# OutputIndicator_v1p4.net
KiCad netlist of a schematic drawn in EAGLE
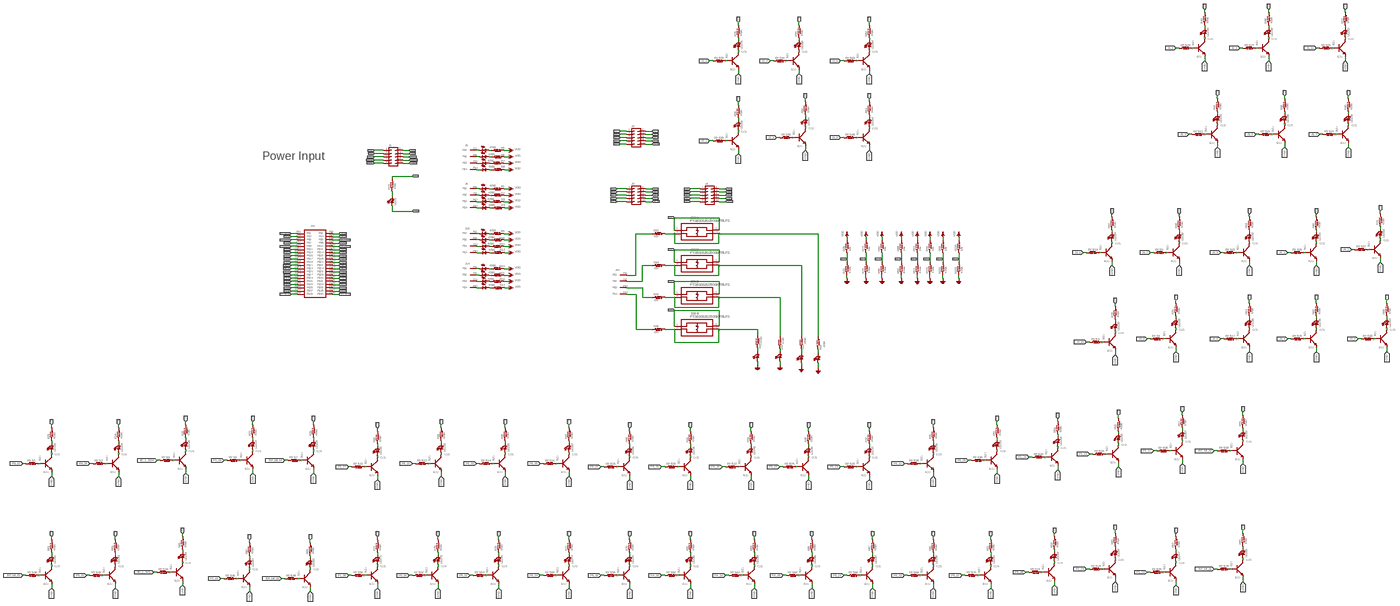
[diagram p0: schematic, sheet 1, overview]
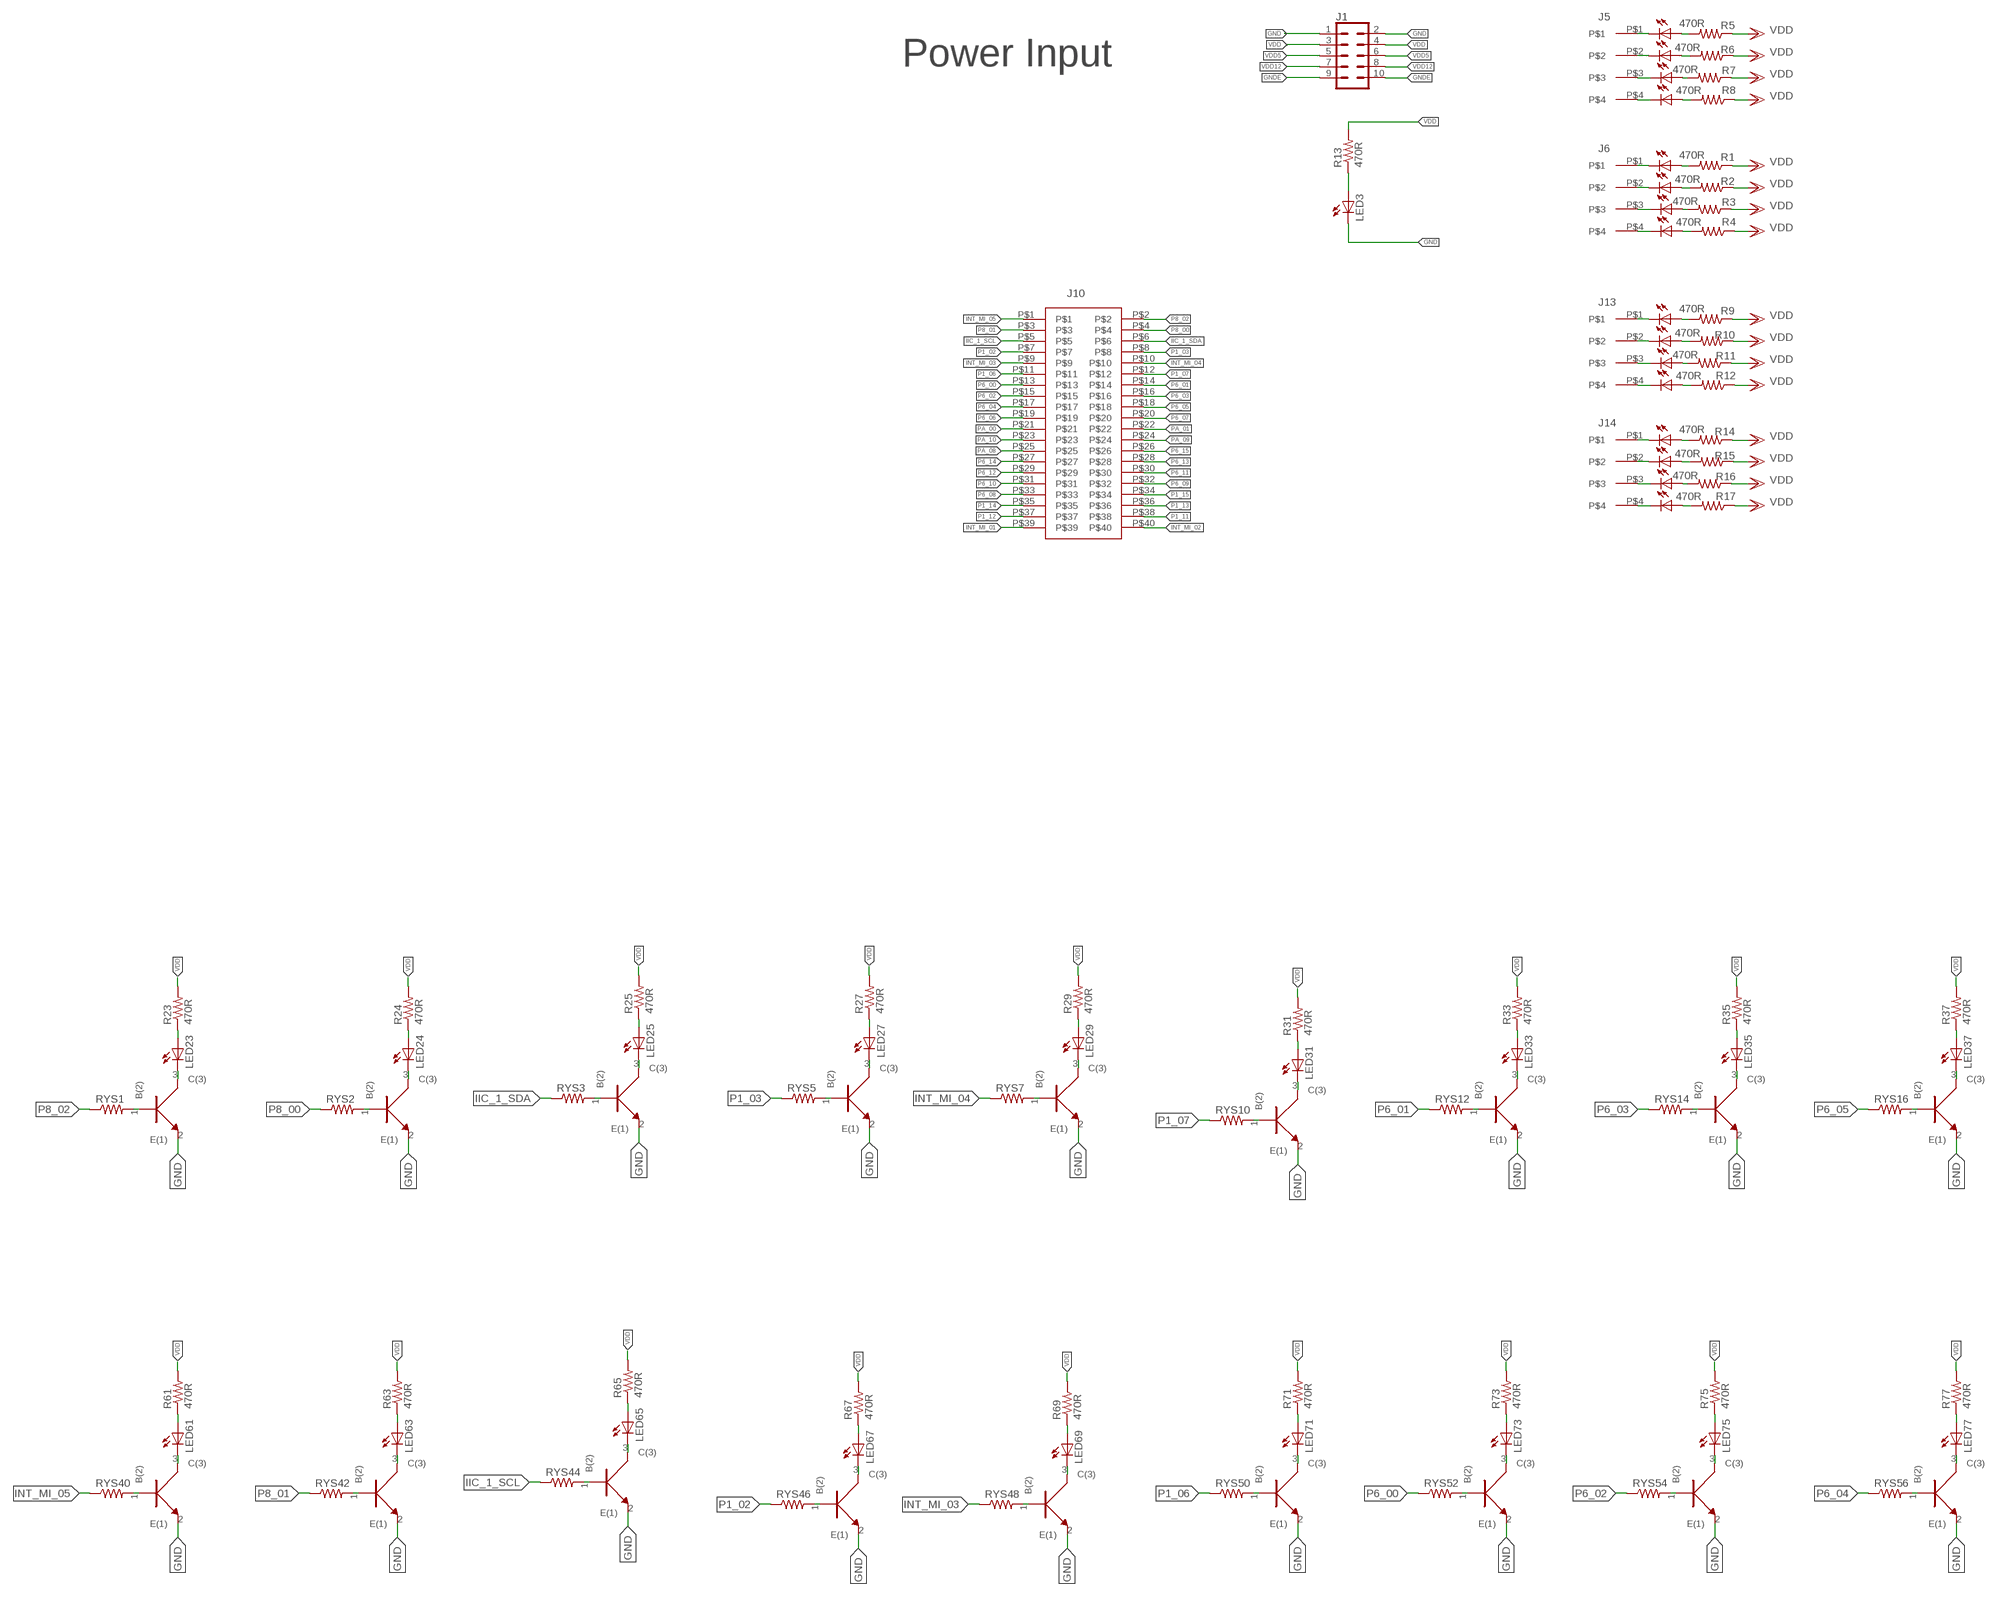
[diagram p1: schematic, sheet 1, part 1 of 5]
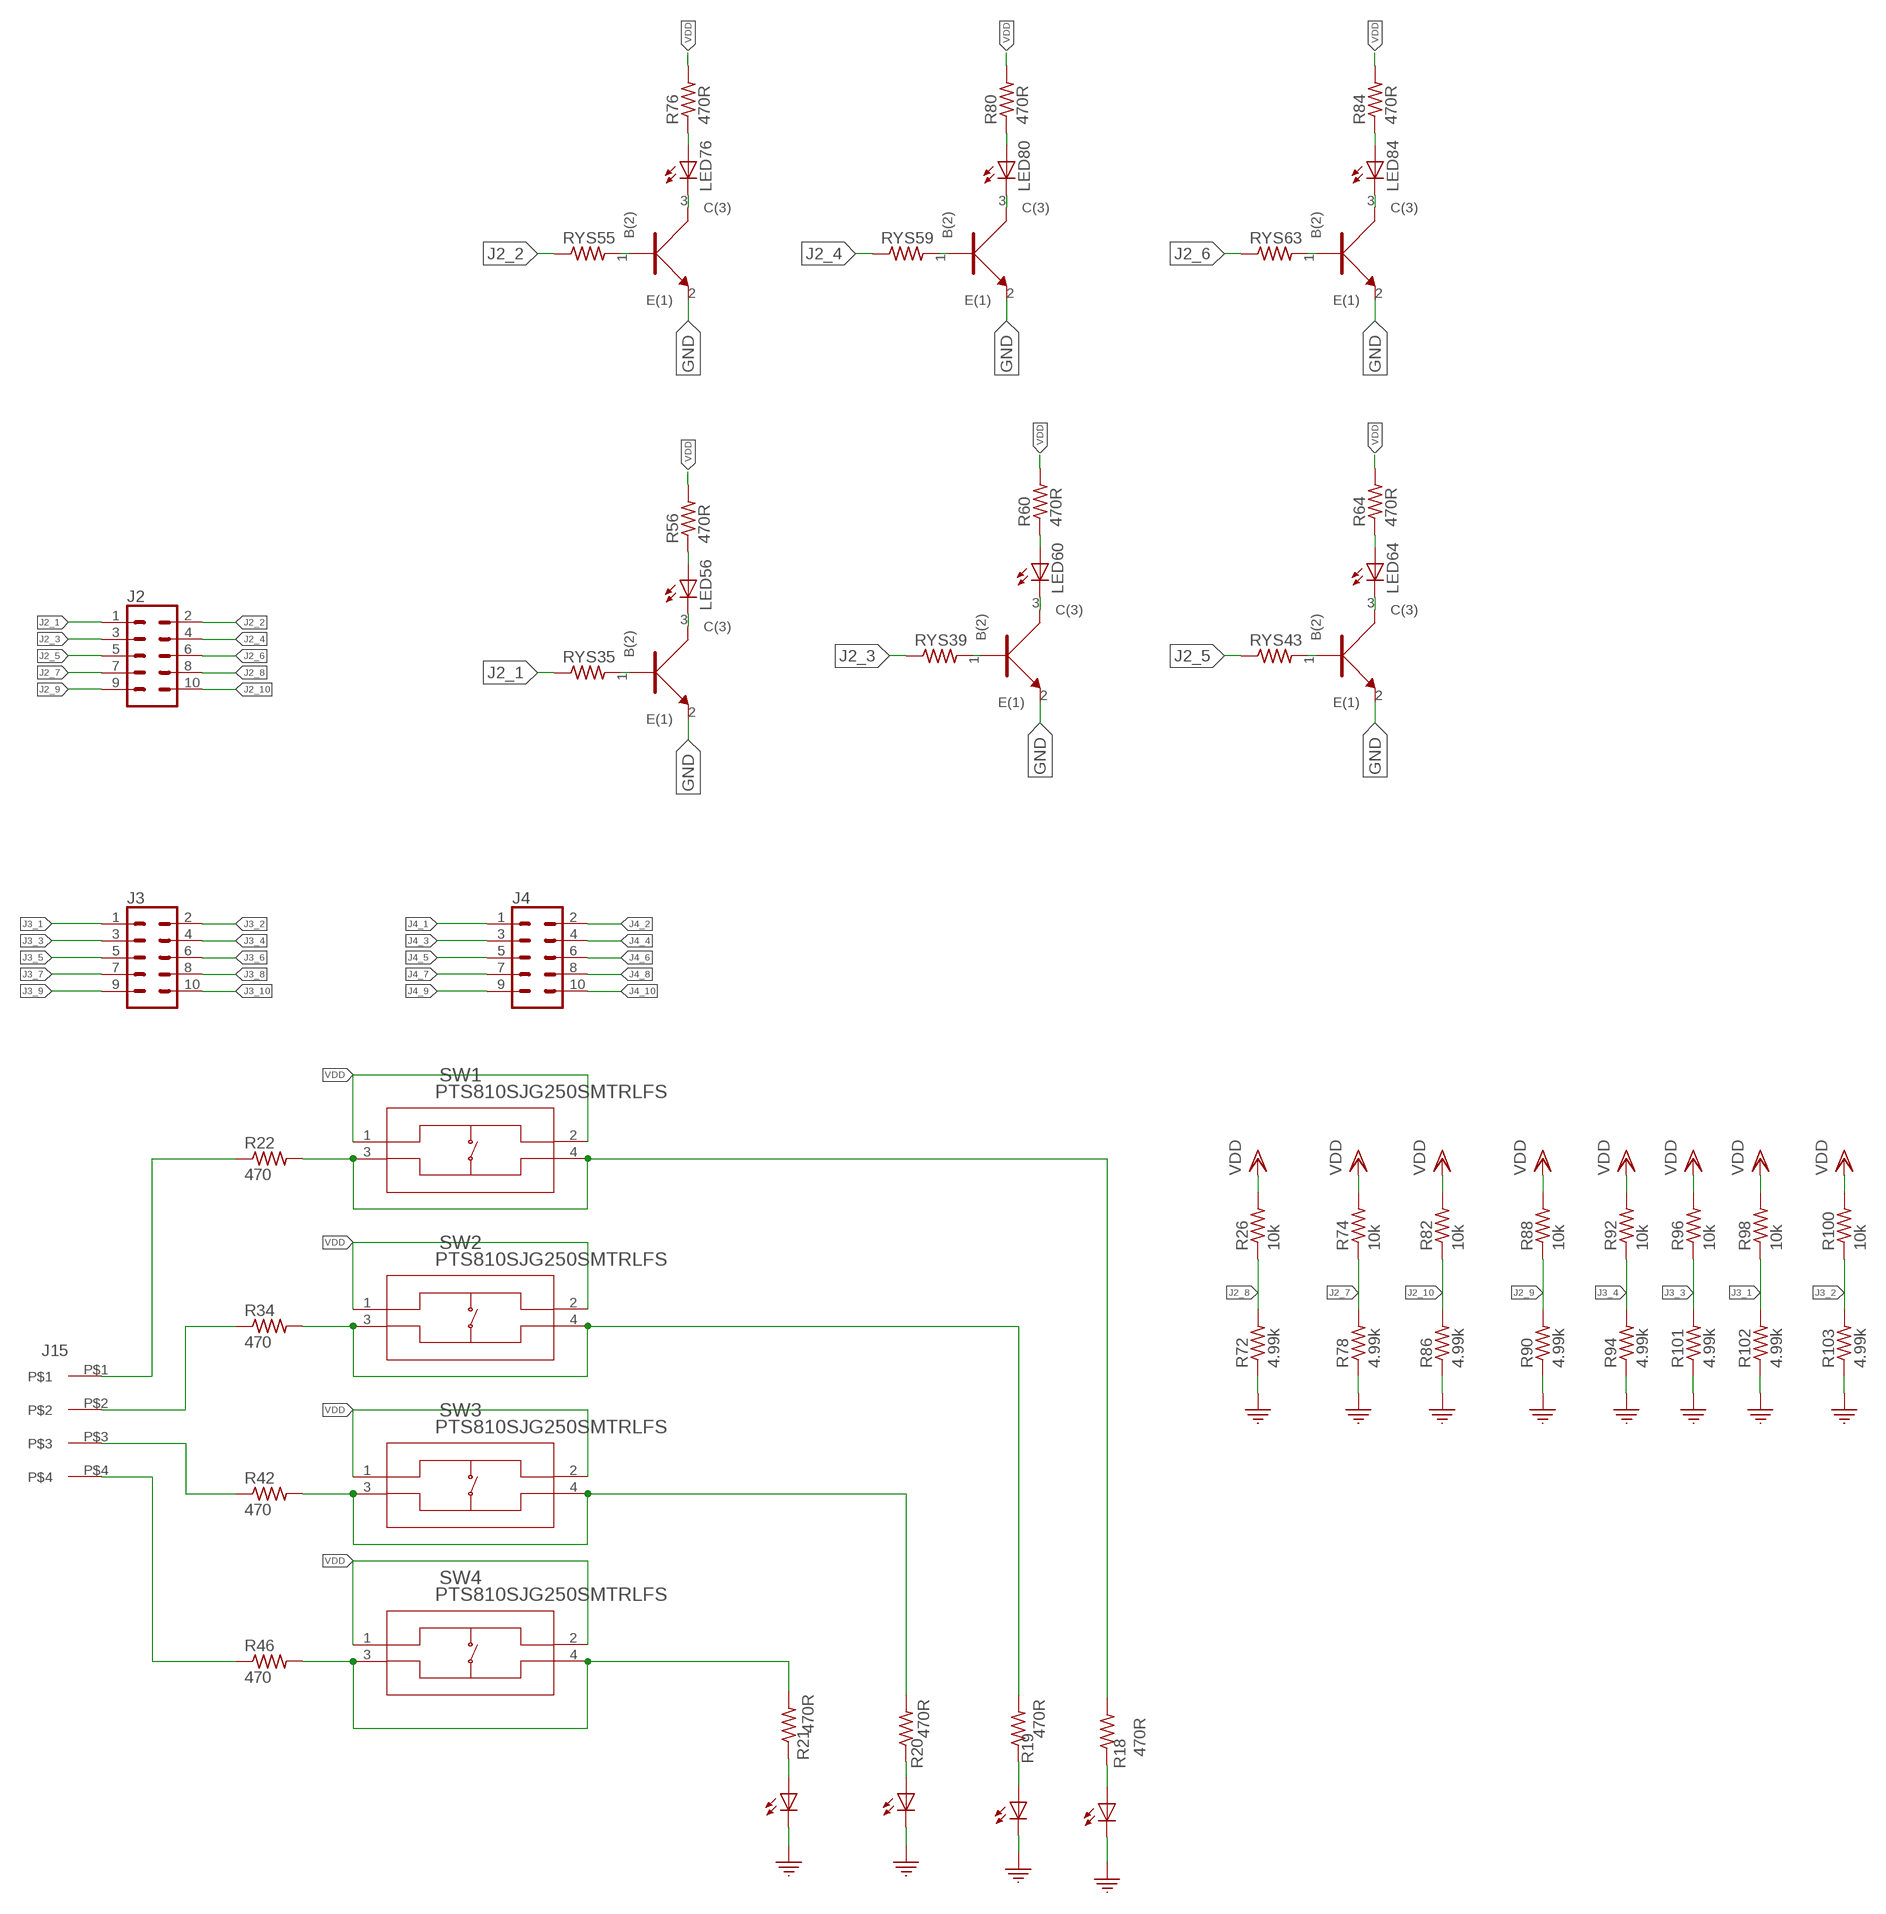
[diagram p2: schematic, sheet 1, part 2 of 5]
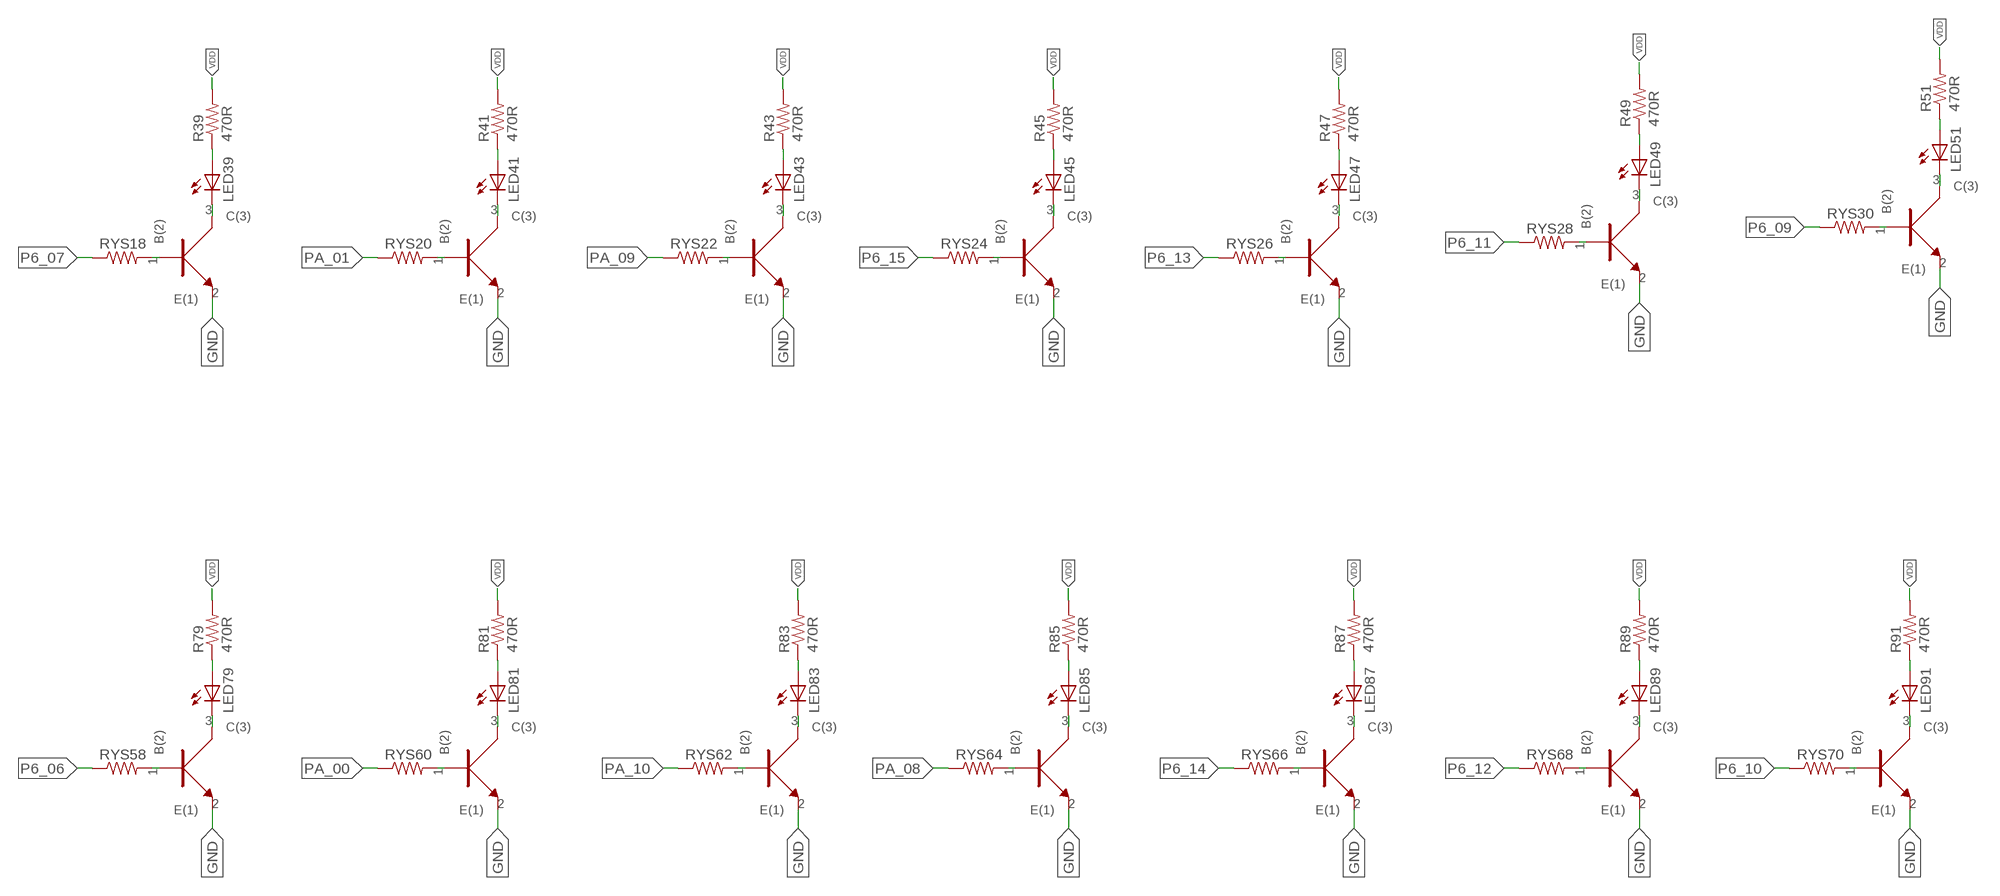
[diagram p3: schematic, sheet 1, part 3 of 5]
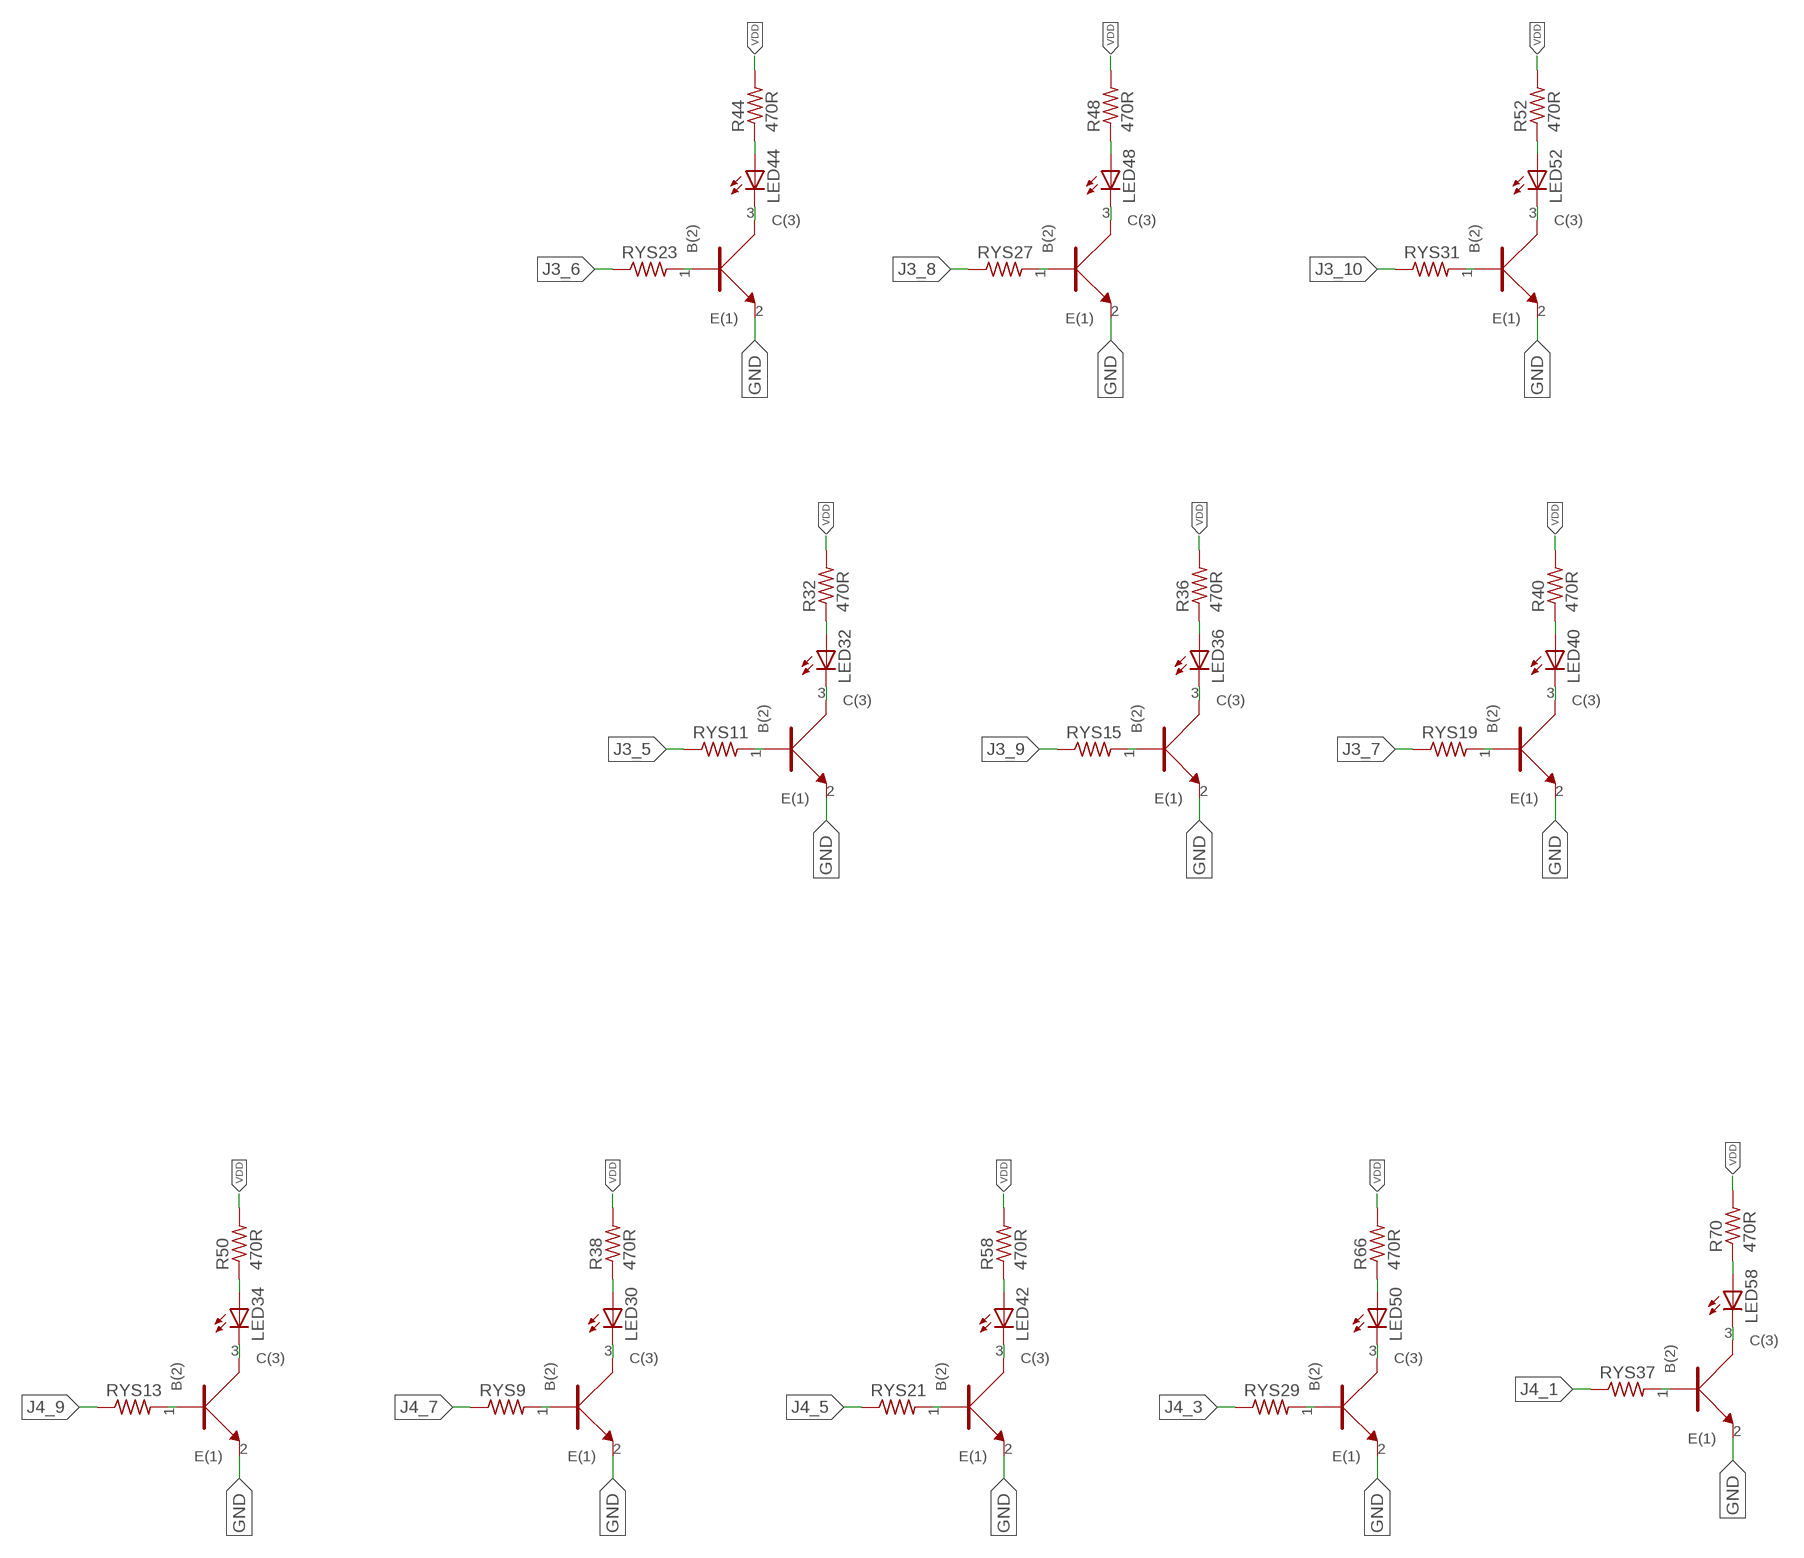
[diagram p4: schematic, sheet 1, part 4 of 5]
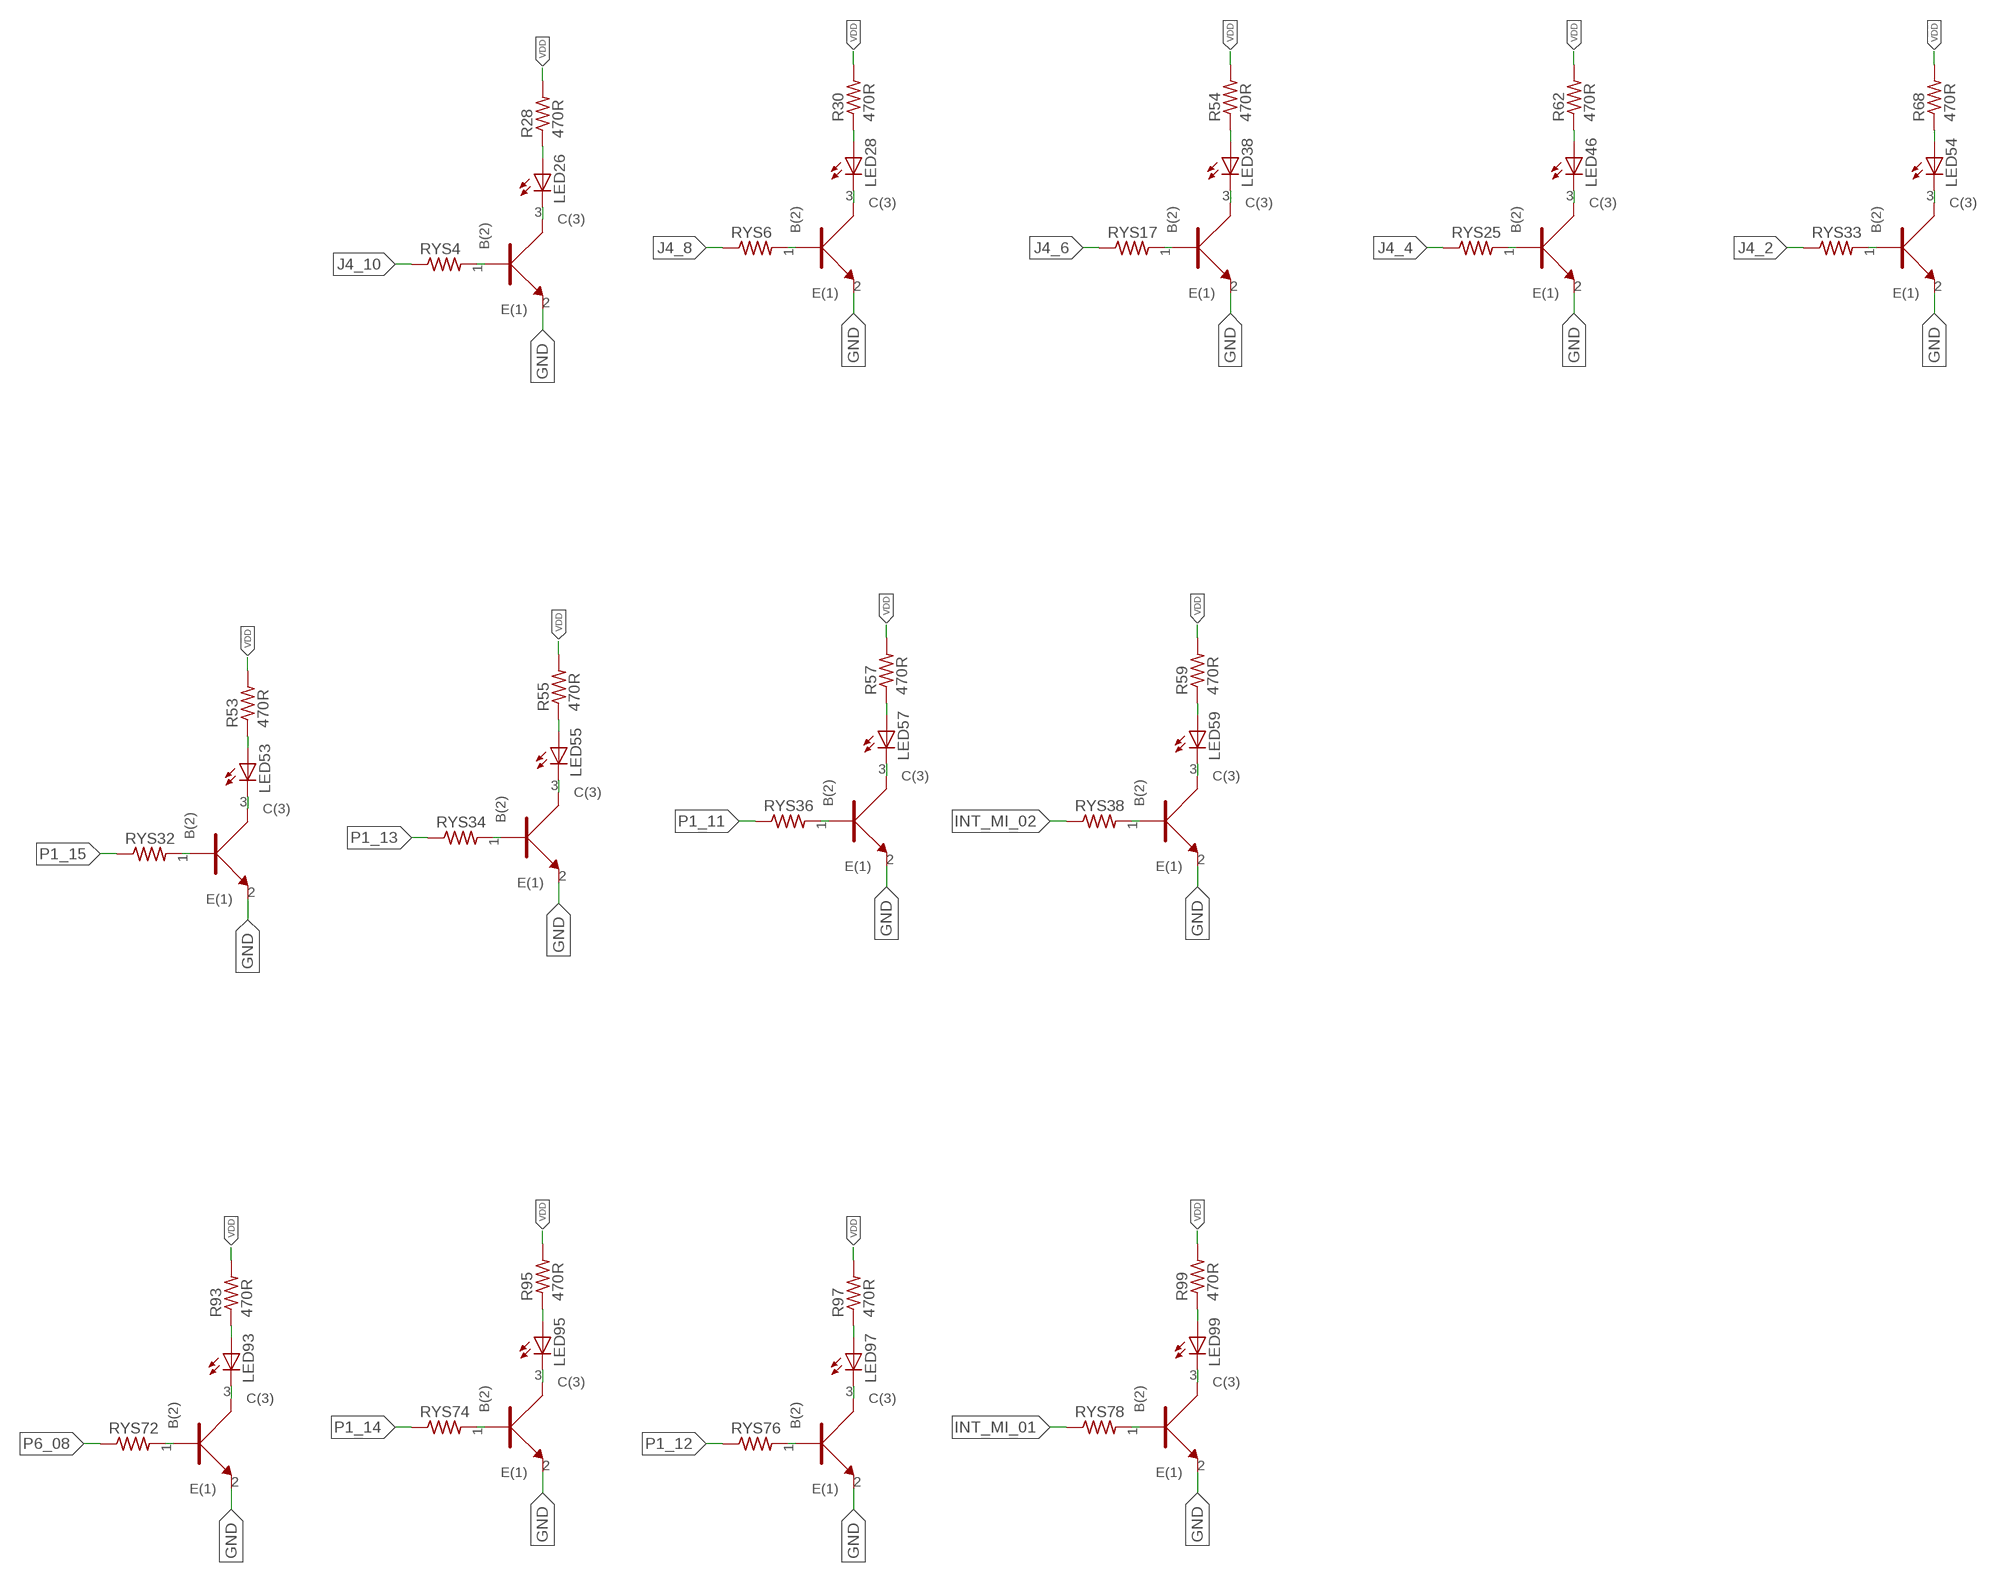
[diagram p5: schematic, sheet 1, part 5 of 5]

(export (version "E")
  (design (tool "Eeschema 10.0.6"))
  (components
    (comp (ref "J1")
      (value "CONN_05X2PTH")
      (footprint "eagle-import:2X5")
      (libsource (lib "eagle-import") (part "CONN_05X2PTH"))
    )
    (comp (ref "J2")
      (value "CONN_05X2PTH")
      (footprint "eagle-import:2X5")
      (libsource (lib "eagle-import") (part "CONN_05X2PTH"))
    )
    (comp (ref "J3")
      (value "CONN_05X2PTH")
      (footprint "eagle-import:2X5")
      (libsource (lib "eagle-import") (part "CONN_05X2PTH"))
    )
    (comp (ref "J4")
      (value "CONN_05X2PTH")
      (footprint "eagle-import:2X5")
      (libsource (lib "eagle-import") (part "CONN_05X2PTH"))
    )
    (comp (ref "J5")
      (value "3.81MM_1_X_4_RT_ANGLE_PLUG_HEADER")
      (footprint "eagle-import:1X4_3.81MM_PITCH")
      (libsource (lib "eagle-import") (part "3.81MM_1_X_4_RT_ANGLE_PLUG_HEADER"))
    )
    (comp (ref "J6")
      (value "3.81MM_1_X_4_RT_ANGLE_PLUG_HEADER")
      (footprint "eagle-import:1X4_3.81MM_PITCH")
      (libsource (lib "eagle-import") (part "3.81MM_1_X_4_RT_ANGLE_PLUG_HEADER"))
    )
    (comp (ref "J10")
      (value "HEADER_2_X_20_GENERIC")
      (footprint "eagle-import:HEADER_2_X_20_.1_INCH")
      (libsource (lib "eagle-import") (part "HEADER_2_X_20_GENERIC"))
    )
    (comp (ref "J13")
      (value "3.81MM_1_X_4_RT_ANGLE_PLUG_HEADER")
      (footprint "eagle-import:1X4_3.81MM_PITCH")
      (libsource (lib "eagle-import") (part "3.81MM_1_X_4_RT_ANGLE_PLUG_HEADER"))
    )
    (comp (ref "J14")
      (value "3.81MM_1_X_4_RT_ANGLE_PLUG_HEADER")
      (footprint "eagle-import:1X4_3.81MM_PITCH")
      (libsource (lib "eagle-import") (part "3.81MM_1_X_4_RT_ANGLE_PLUG_HEADER"))
    )
    (comp (ref "J15")
      (value "3.81MM_1_X_4_RT_ANGLE_PLUG_HEADER")
      (footprint "eagle-import:1X4_3.81MM_PITCH")
      (libsource (lib "eagle-import") (part "3.81MM_1_X_4_RT_ANGLE_PLUG_HEADER"))
    )
    (comp (ref "LED1")
      (value "LED_0805_GREEN")
      (footprint "eagle-import:LED_0805_GREEN")
      (libsource (lib "eagle-import") (part "LED_0805_GREEN"))
    )
    (comp (ref "LED2")
      (value "LED_0805_GREEN")
      (footprint "eagle-import:LED_0805_GREEN")
      (libsource (lib "eagle-import") (part "LED_0805_GREEN"))
    )
    (comp (ref "LED3")
      (value "LED_0805_GREEN")
      (footprint "eagle-import:LED_0805_GREEN")
      (libsource (lib "eagle-import") (part "LED_0805_GREEN"))
    )
    (comp (ref "LED4")
      (value "LED_0805_GREEN")
      (footprint "eagle-import:LED_0805_GREEN")
      (libsource (lib "eagle-import") (part "LED_0805_GREEN"))
    )
    (comp (ref "LED5")
      (value "LED_0805_GREEN")
      (footprint "eagle-import:LED_0805_GREEN")
      (libsource (lib "eagle-import") (part "LED_0805_GREEN"))
    )
    (comp (ref "LED6")
      (value "LED_0805_GREEN")
      (footprint "eagle-import:LED_0805_GREEN")
      (libsource (lib "eagle-import") (part "LED_0805_GREEN"))
    )
    (comp (ref "LED7")
      (value "LED_0805_GREEN")
      (footprint "eagle-import:LED_0805_GREEN")
      (libsource (lib "eagle-import") (part "LED_0805_GREEN"))
    )
    (comp (ref "LED8")
      (value "LED_0805_GREEN")
      (footprint "eagle-import:LED_0805_GREEN")
      (libsource (lib "eagle-import") (part "LED_0805_GREEN"))
    )
    (comp (ref "LED9")
      (value "LED_0805_GREEN")
      (footprint "eagle-import:LED_0805_GREEN")
      (libsource (lib "eagle-import") (part "LED_0805_GREEN"))
    )
    (comp (ref "LED10")
      (value "LED_0805_GREEN")
      (footprint "eagle-import:LED_0805_GREEN")
      (libsource (lib "eagle-import") (part "LED_0805_GREEN"))
    )
    (comp (ref "LED11")
      (value "LED_0805_GREEN")
      (footprint "eagle-import:LED_0805_GREEN")
      (libsource (lib "eagle-import") (part "LED_0805_GREEN"))
    )
    (comp (ref "LED12")
      (value "LED_0805_GREEN")
      (footprint "eagle-import:LED_0805_GREEN")
      (libsource (lib "eagle-import") (part "LED_0805_GREEN"))
    )
    (comp (ref "LED13")
      (value "LED_0805_GREEN")
      (footprint "eagle-import:LED_0805_GREEN")
      (libsource (lib "eagle-import") (part "LED_0805_GREEN"))
    )
    (comp (ref "LED14")
      (value "LED_0805_GREEN")
      (footprint "eagle-import:LED_0805_GREEN")
      (libsource (lib "eagle-import") (part "LED_0805_GREEN"))
    )
    (comp (ref "LED15")
      (value "LED_0805_GREEN")
      (footprint "eagle-import:LED_0805_GREEN")
      (libsource (lib "eagle-import") (part "LED_0805_GREEN"))
    )
    (comp (ref "LED16")
      (value "LED_0805_GREEN")
      (footprint "eagle-import:LED_0805_GREEN")
      (libsource (lib "eagle-import") (part "LED_0805_GREEN"))
    )
    (comp (ref "LED17")
      (value "LED_0805_GREEN")
      (footprint "eagle-import:LED_0805_GREEN")
      (libsource (lib "eagle-import") (part "LED_0805_GREEN"))
    )
    (comp (ref "LED18")
      (value "LED_0805_GREEN")
      (footprint "eagle-import:LED_0805_GREEN")
      (libsource (lib "eagle-import") (part "LED_0805_GREEN"))
    )
    (comp (ref "LED19")
      (value "LED_0805_GREEN")
      (footprint "eagle-import:LED_0805_GREEN")
      (libsource (lib "eagle-import") (part "LED_0805_GREEN"))
    )
    (comp (ref "LED20")
      (value "LED_0805_GREEN")
      (footprint "eagle-import:LED_0805_GREEN")
      (libsource (lib "eagle-import") (part "LED_0805_GREEN"))
    )
    (comp (ref "LED21")
      (value "LED_0805_GREEN")
      (footprint "eagle-import:LED_0805_GREEN")
      (libsource (lib "eagle-import") (part "LED_0805_GREEN"))
    )
    (comp (ref "LED23")
      (value "LED_0805_GREEN")
      (footprint "eagle-import:LED_0805_GREEN")
      (libsource (lib "eagle-import") (part "LED_0805_GREEN"))
    )
    (comp (ref "LED24")
      (value "LED_0805_GREEN")
      (footprint "eagle-import:LED_0805_GREEN")
      (libsource (lib "eagle-import") (part "LED_0805_GREEN"))
    )
    (comp (ref "LED25")
      (value "LED_0805_GREEN")
      (footprint "eagle-import:LED_0805_GREEN")
      (libsource (lib "eagle-import") (part "LED_0805_GREEN"))
    )
    (comp (ref "LED26")
      (value "LED_0805_GREEN")
      (footprint "eagle-import:LED_0805_GREEN")
      (libsource (lib "eagle-import") (part "LED_0805_GREEN"))
    )
    (comp (ref "LED27")
      (value "LED_0805_GREEN")
      (footprint "eagle-import:LED_0805_GREEN")
      (libsource (lib "eagle-import") (part "LED_0805_GREEN"))
    )
    (comp (ref "LED28")
      (value "LED_0805_GREEN")
      (footprint "eagle-import:LED_0805_GREEN")
      (libsource (lib "eagle-import") (part "LED_0805_GREEN"))
    )
    (comp (ref "LED29")
      (value "LED_0805_GREEN")
      (footprint "eagle-import:LED_0805_GREEN")
      (libsource (lib "eagle-import") (part "LED_0805_GREEN"))
    )
    (comp (ref "LED30")
      (value "LED_0805_GREEN")
      (footprint "eagle-import:LED_0805_GREEN")
      (libsource (lib "eagle-import") (part "LED_0805_GREEN"))
    )
    (comp (ref "LED31")
      (value "LED_0805_GREEN")
      (footprint "eagle-import:LED_0805_GREEN")
      (libsource (lib "eagle-import") (part "LED_0805_GREEN"))
    )
    (comp (ref "LED32")
      (value "LED_0805_GREEN")
      (footprint "eagle-import:LED_0805_GREEN")
      (libsource (lib "eagle-import") (part "LED_0805_GREEN"))
    )
    (comp (ref "LED33")
      (value "LED_0805_GREEN")
      (footprint "eagle-import:LED_0805_GREEN")
      (libsource (lib "eagle-import") (part "LED_0805_GREEN"))
    )
    (comp (ref "LED34")
      (value "LED_0805_GREEN")
      (footprint "eagle-import:LED_0805_GREEN")
      (libsource (lib "eagle-import") (part "LED_0805_GREEN"))
    )
    (comp (ref "LED35")
      (value "LED_0805_GREEN")
      (footprint "eagle-import:LED_0805_GREEN")
      (libsource (lib "eagle-import") (part "LED_0805_GREEN"))
    )
    (comp (ref "LED36")
      (value "LED_0805_GREEN")
      (footprint "eagle-import:LED_0805_GREEN")
      (libsource (lib "eagle-import") (part "LED_0805_GREEN"))
    )
    (comp (ref "LED37")
      (value "LED_0805_GREEN")
      (footprint "eagle-import:LED_0805_GREEN")
      (libsource (lib "eagle-import") (part "LED_0805_GREEN"))
    )
    (comp (ref "LED38")
      (value "LED_0805_GREEN")
      (footprint "eagle-import:LED_0805_GREEN")
      (libsource (lib "eagle-import") (part "LED_0805_GREEN"))
    )
    (comp (ref "LED39")
      (value "LED_0805_GREEN")
      (footprint "eagle-import:LED_0805_GREEN")
      (libsource (lib "eagle-import") (part "LED_0805_GREEN"))
    )
    (comp (ref "LED40")
      (value "LED_0805_GREEN")
      (footprint "eagle-import:LED_0805_GREEN")
      (libsource (lib "eagle-import") (part "LED_0805_GREEN"))
    )
    (comp (ref "LED41")
      (value "LED_0805_GREEN")
      (footprint "eagle-import:LED_0805_GREEN")
      (libsource (lib "eagle-import") (part "LED_0805_GREEN"))
    )
    (comp (ref "LED42")
      (value "LED_0805_GREEN")
      (footprint "eagle-import:LED_0805_GREEN")
      (libsource (lib "eagle-import") (part "LED_0805_GREEN"))
    )
    (comp (ref "LED43")
      (value "LED_0805_GREEN")
      (footprint "eagle-import:LED_0805_GREEN")
      (libsource (lib "eagle-import") (part "LED_0805_GREEN"))
    )
    (comp (ref "LED44")
      (value "LED_0805_GREEN")
      (footprint "eagle-import:LED_0805_GREEN")
      (libsource (lib "eagle-import") (part "LED_0805_GREEN"))
    )
    (comp (ref "LED45")
      (value "LED_0805_GREEN")
      (footprint "eagle-import:LED_0805_GREEN")
      (libsource (lib "eagle-import") (part "LED_0805_GREEN"))
    )
    (comp (ref "LED46")
      (value "LED_0805_GREEN")
      (footprint "eagle-import:LED_0805_GREEN")
      (libsource (lib "eagle-import") (part "LED_0805_GREEN"))
    )
    (comp (ref "LED47")
      (value "LED_0805_GREEN")
      (footprint "eagle-import:LED_0805_GREEN")
      (libsource (lib "eagle-import") (part "LED_0805_GREEN"))
    )
    (comp (ref "LED48")
      (value "LED_0805_GREEN")
      (footprint "eagle-import:LED_0805_GREEN")
      (libsource (lib "eagle-import") (part "LED_0805_GREEN"))
    )
    (comp (ref "LED49")
      (value "LED_0805_GREEN")
      (footprint "eagle-import:LED_0805_GREEN")
      (libsource (lib "eagle-import") (part "LED_0805_GREEN"))
    )
    (comp (ref "LED50")
      (value "LED_0805_GREEN")
      (footprint "eagle-import:LED_0805_GREEN")
      (libsource (lib "eagle-import") (part "LED_0805_GREEN"))
    )
    (comp (ref "LED51")
      (value "LED_0805_GREEN")
      (footprint "eagle-import:LED_0805_GREEN")
      (libsource (lib "eagle-import") (part "LED_0805_GREEN"))
    )
    (comp (ref "LED52")
      (value "LED_0805_GREEN")
      (footprint "eagle-import:LED_0805_GREEN")
      (libsource (lib "eagle-import") (part "LED_0805_GREEN"))
    )
    (comp (ref "LED53")
      (value "LED_0805_GREEN")
      (footprint "eagle-import:LED_0805_GREEN")
      (libsource (lib "eagle-import") (part "LED_0805_GREEN"))
    )
    (comp (ref "LED54")
      (value "LED_0805_GREEN")
      (footprint "eagle-import:LED_0805_GREEN")
      (libsource (lib "eagle-import") (part "LED_0805_GREEN"))
    )
    (comp (ref "LED55")
      (value "LED_0805_GREEN")
      (footprint "eagle-import:LED_0805_GREEN")
      (libsource (lib "eagle-import") (part "LED_0805_GREEN"))
    )
    (comp (ref "LED56")
      (value "LED_0805_GREEN")
      (footprint "eagle-import:LED_0805_GREEN")
      (libsource (lib "eagle-import") (part "LED_0805_GREEN"))
    )
    (comp (ref "LED57")
      (value "LED_0805_GREEN")
      (footprint "eagle-import:LED_0805_GREEN")
      (libsource (lib "eagle-import") (part "LED_0805_GREEN"))
    )
    (comp (ref "LED58")
      (value "LED_0805_GREEN")
      (footprint "eagle-import:LED_0805_GREEN")
      (libsource (lib "eagle-import") (part "LED_0805_GREEN"))
    )
    (comp (ref "LED59")
      (value "LED_0805_GREEN")
      (footprint "eagle-import:LED_0805_GREEN")
      (libsource (lib "eagle-import") (part "LED_0805_GREEN"))
    )
    (comp (ref "LED60")
      (value "LED_0805_GREEN")
      (footprint "eagle-import:LED_0805_GREEN")
      (libsource (lib "eagle-import") (part "LED_0805_GREEN"))
    )
    (comp (ref "LED61")
      (value "LED_0805_GREEN")
      (footprint "eagle-import:LED_0805_GREEN")
      (libsource (lib "eagle-import") (part "LED_0805_GREEN"))
    )
    (comp (ref "LED63")
      (value "LED_0805_GREEN")
      (footprint "eagle-import:LED_0805_GREEN")
      (libsource (lib "eagle-import") (part "LED_0805_GREEN"))
    )
    (comp (ref "LED64")
      (value "LED_0805_GREEN")
      (footprint "eagle-import:LED_0805_GREEN")
      (libsource (lib "eagle-import") (part "LED_0805_GREEN"))
    )
    (comp (ref "LED65")
      (value "LED_0805_GREEN")
      (footprint "eagle-import:LED_0805_GREEN")
      (libsource (lib "eagle-import") (part "LED_0805_GREEN"))
    )
    (comp (ref "LED67")
      (value "LED_0805_GREEN")
      (footprint "eagle-import:LED_0805_GREEN")
      (libsource (lib "eagle-import") (part "LED_0805_GREEN"))
    )
    (comp (ref "LED69")
      (value "LED_0805_GREEN")
      (footprint "eagle-import:LED_0805_GREEN")
      (libsource (lib "eagle-import") (part "LED_0805_GREEN"))
    )
    (comp (ref "LED71")
      (value "LED_0805_GREEN")
      (footprint "eagle-import:LED_0805_GREEN")
      (libsource (lib "eagle-import") (part "LED_0805_GREEN"))
    )
    (comp (ref "LED73")
      (value "LED_0805_GREEN")
      (footprint "eagle-import:LED_0805_GREEN")
      (libsource (lib "eagle-import") (part "LED_0805_GREEN"))
    )
    (comp (ref "LED75")
      (value "LED_0805_GREEN")
      (footprint "eagle-import:LED_0805_GREEN")
      (libsource (lib "eagle-import") (part "LED_0805_GREEN"))
    )
    (comp (ref "LED76")
      (value "LED_0805_GREEN")
      (footprint "eagle-import:LED_0805_GREEN")
      (libsource (lib "eagle-import") (part "LED_0805_GREEN"))
    )
    (comp (ref "LED77")
      (value "LED_0805_GREEN")
      (footprint "eagle-import:LED_0805_GREEN")
      (libsource (lib "eagle-import") (part "LED_0805_GREEN"))
    )
    (comp (ref "LED79")
      (value "LED_0805_GREEN")
      (footprint "eagle-import:LED_0805_GREEN")
      (libsource (lib "eagle-import") (part "LED_0805_GREEN"))
    )
    (comp (ref "LED80")
      (value "LED_0805_GREEN")
      (footprint "eagle-import:LED_0805_GREEN")
      (libsource (lib "eagle-import") (part "LED_0805_GREEN"))
    )
    (comp (ref "LED81")
      (value "LED_0805_GREEN")
      (footprint "eagle-import:LED_0805_GREEN")
      (libsource (lib "eagle-import") (part "LED_0805_GREEN"))
    )
    (comp (ref "LED83")
      (value "LED_0805_GREEN")
      (footprint "eagle-import:LED_0805_GREEN")
      (libsource (lib "eagle-import") (part "LED_0805_GREEN"))
    )
    (comp (ref "LED84")
      (value "LED_0805_GREEN")
      (footprint "eagle-import:LED_0805_GREEN")
      (libsource (lib "eagle-import") (part "LED_0805_GREEN"))
    )
    (comp (ref "LED85")
      (value "LED_0805_GREEN")
      (footprint "eagle-import:LED_0805_GREEN")
      (libsource (lib "eagle-import") (part "LED_0805_GREEN"))
    )
    (comp (ref "LED87")
      (value "LED_0805_GREEN")
      (footprint "eagle-import:LED_0805_GREEN")
      (libsource (lib "eagle-import") (part "LED_0805_GREEN"))
    )
    (comp (ref "LED89")
      (value "LED_0805_GREEN")
      (footprint "eagle-import:LED_0805_GREEN")
      (libsource (lib "eagle-import") (part "LED_0805_GREEN"))
    )
    (comp (ref "LED91")
      (value "LED_0805_GREEN")
      (footprint "eagle-import:LED_0805_GREEN")
      (libsource (lib "eagle-import") (part "LED_0805_GREEN"))
    )
    (comp (ref "LED93")
      (value "LED_0805_GREEN")
      (footprint "eagle-import:LED_0805_GREEN")
      (libsource (lib "eagle-import") (part "LED_0805_GREEN"))
    )
    (comp (ref "LED95")
      (value "LED_0805_GREEN")
      (footprint "eagle-import:LED_0805_GREEN")
      (libsource (lib "eagle-import") (part "LED_0805_GREEN"))
    )
    (comp (ref "LED97")
      (value "LED_0805_GREEN")
      (footprint "eagle-import:LED_0805_GREEN")
      (libsource (lib "eagle-import") (part "LED_0805_GREEN"))
    )
    (comp (ref "LED99")
      (value "LED_0805_GREEN")
      (footprint "eagle-import:LED_0805_GREEN")
      (libsource (lib "eagle-import") (part "LED_0805_GREEN"))
    )
    (comp (ref "R1")
      (value "470R")
      (footprint "eagle-import:0402")
      (libsource (lib "eagle-import") (part "R_0402"))
    )
    (comp (ref "R2")
      (value "470R")
      (footprint "eagle-import:0402")
      (libsource (lib "eagle-import") (part "R_0402"))
    )
    (comp (ref "R3")
      (value "470R")
      (footprint "eagle-import:0402")
      (libsource (lib "eagle-import") (part "R_0402"))
    )
    (comp (ref "R4")
      (value "470R")
      (footprint "eagle-import:0402")
      (libsource (lib "eagle-import") (part "R_0402"))
    )
    (comp (ref "R5")
      (value "470R")
      (footprint "eagle-import:0402")
      (libsource (lib "eagle-import") (part "R_0402"))
    )
    (comp (ref "R6")
      (value "470R")
      (footprint "eagle-import:0402")
      (libsource (lib "eagle-import") (part "R_0402"))
    )
    (comp (ref "R7")
      (value "470R")
      (footprint "eagle-import:0402")
      (libsource (lib "eagle-import") (part "R_0402"))
    )
    (comp (ref "R8")
      (value "470R")
      (footprint "eagle-import:0402")
      (libsource (lib "eagle-import") (part "R_0402"))
    )
    (comp (ref "R9")
      (value "470R")
      (footprint "eagle-import:0402")
      (libsource (lib "eagle-import") (part "R_0402"))
    )
    (comp (ref "R10")
      (value "470R")
      (footprint "eagle-import:0402")
      (libsource (lib "eagle-import") (part "R_0402"))
    )
    (comp (ref "R11")
      (value "470R")
      (footprint "eagle-import:0402")
      (libsource (lib "eagle-import") (part "R_0402"))
    )
    (comp (ref "R12")
      (value "470R")
      (footprint "eagle-import:0402")
      (libsource (lib "eagle-import") (part "R_0402"))
    )
    (comp (ref "R13")
      (value "470R")
      (footprint "eagle-import:0402")
      (libsource (lib "eagle-import") (part "R_0402"))
    )
    (comp (ref "R14")
      (value "470R")
      (footprint "eagle-import:0402")
      (libsource (lib "eagle-import") (part "R_0402"))
    )
    (comp (ref "R15")
      (value "470R")
      (footprint "eagle-import:0402")
      (libsource (lib "eagle-import") (part "R_0402"))
    )
    (comp (ref "R16")
      (value "470R")
      (footprint "eagle-import:0402")
      (libsource (lib "eagle-import") (part "R_0402"))
    )
    (comp (ref "R17")
      (value "470R")
      (footprint "eagle-import:0402")
      (libsource (lib "eagle-import") (part "R_0402"))
    )
    (comp (ref "R18")
      (value "470R")
      (footprint "eagle-import:0402")
      (libsource (lib "eagle-import") (part "R_0402"))
    )
    (comp (ref "R19")
      (value "470R")
      (footprint "eagle-import:0402")
      (libsource (lib "eagle-import") (part "R_0402"))
    )
    (comp (ref "R20")
      (value "470R")
      (footprint "eagle-import:0402")
      (libsource (lib "eagle-import") (part "R_0402"))
    )
    (comp (ref "R21")
      (value "470R")
      (footprint "eagle-import:0402")
      (libsource (lib "eagle-import") (part "R_0402"))
    )
    (comp (ref "R22")
      (value "470")
      (footprint "eagle-import:0402")
      (libsource (lib "eagle-import") (part "R_0402"))
    )
    (comp (ref "R23")
      (value "470R")
      (footprint "eagle-import:0402")
      (libsource (lib "eagle-import") (part "R_0402"))
    )
    (comp (ref "R24")
      (value "470R")
      (footprint "eagle-import:0402")
      (libsource (lib "eagle-import") (part "R_0402"))
    )
    (comp (ref "R25")
      (value "470R")
      (footprint "eagle-import:0402")
      (libsource (lib "eagle-import") (part "R_0402"))
    )
    (comp (ref "R26")
      (value "10k")
      (footprint "eagle-import:0805")
      (libsource (lib "eagle-import") (part "R_0805"))
    )
    (comp (ref "R27")
      (value "470R")
      (footprint "eagle-import:0402")
      (libsource (lib "eagle-import") (part "R_0402"))
    )
    (comp (ref "R28")
      (value "470R")
      (footprint "eagle-import:0402")
      (libsource (lib "eagle-import") (part "R_0402"))
    )
    (comp (ref "R29")
      (value "470R")
      (footprint "eagle-import:0402")
      (libsource (lib "eagle-import") (part "R_0402"))
    )
    (comp (ref "R30")
      (value "470R")
      (footprint "eagle-import:0402")
      (libsource (lib "eagle-import") (part "R_0402"))
    )
    (comp (ref "R31")
      (value "470R")
      (footprint "eagle-import:0402")
      (libsource (lib "eagle-import") (part "R_0402"))
    )
    (comp (ref "R32")
      (value "470R")
      (footprint "eagle-import:0402")
      (libsource (lib "eagle-import") (part "R_0402"))
    )
    (comp (ref "R33")
      (value "470R")
      (footprint "eagle-import:0402")
      (libsource (lib "eagle-import") (part "R_0402"))
    )
    (comp (ref "R34")
      (value "470")
      (footprint "eagle-import:0402")
      (libsource (lib "eagle-import") (part "R_0402"))
    )
    (comp (ref "R35")
      (value "470R")
      (footprint "eagle-import:0402")
      (libsource (lib "eagle-import") (part "R_0402"))
    )
    (comp (ref "R36")
      (value "470R")
      (footprint "eagle-import:0402")
      (libsource (lib "eagle-import") (part "R_0402"))
    )
    (comp (ref "R37")
      (value "470R")
      (footprint "eagle-import:0402")
      (libsource (lib "eagle-import") (part "R_0402"))
    )
    (comp (ref "R38")
      (value "470R")
      (footprint "eagle-import:0402")
      (libsource (lib "eagle-import") (part "R_0402"))
    )
    (comp (ref "R39")
      (value "470R")
      (footprint "eagle-import:0402")
      (libsource (lib "eagle-import") (part "R_0402"))
    )
    (comp (ref "R40")
      (value "470R")
      (footprint "eagle-import:0402")
      (libsource (lib "eagle-import") (part "R_0402"))
    )
    (comp (ref "R41")
      (value "470R")
      (footprint "eagle-import:0402")
      (libsource (lib "eagle-import") (part "R_0402"))
    )
    (comp (ref "R42")
      (value "470")
      (footprint "eagle-import:0402")
      (libsource (lib "eagle-import") (part "R_0402"))
    )
    (comp (ref "R43")
      (value "470R")
      (footprint "eagle-import:0402")
      (libsource (lib "eagle-import") (part "R_0402"))
    )
    (comp (ref "R44")
      (value "470R")
      (footprint "eagle-import:0402")
      (libsource (lib "eagle-import") (part "R_0402"))
    )
    (comp (ref "R45")
      (value "470R")
      (footprint "eagle-import:0402")
      (libsource (lib "eagle-import") (part "R_0402"))
    )
    (comp (ref "R46")
      (value "470")
      (footprint "eagle-import:0402")
      (libsource (lib "eagle-import") (part "R_0402"))
    )
    (comp (ref "R47")
      (value "470R")
      (footprint "eagle-import:0402")
      (libsource (lib "eagle-import") (part "R_0402"))
    )
    (comp (ref "R48")
      (value "470R")
      (footprint "eagle-import:0402")
      (libsource (lib "eagle-import") (part "R_0402"))
    )
    (comp (ref "R49")
      (value "470R")
      (footprint "eagle-import:0402")
      (libsource (lib "eagle-import") (part "R_0402"))
    )
    (comp (ref "R50")
      (value "470R")
      (footprint "eagle-import:0402")
      (libsource (lib "eagle-import") (part "R_0402"))
    )
    (comp (ref "R51")
      (value "470R")
      (footprint "eagle-import:0402")
      (libsource (lib "eagle-import") (part "R_0402"))
    )
    (comp (ref "R52")
      (value "470R")
      (footprint "eagle-import:0402")
      (libsource (lib "eagle-import") (part "R_0402"))
    )
    (comp (ref "R53")
      (value "470R")
      (footprint "eagle-import:0402")
      (libsource (lib "eagle-import") (part "R_0402"))
    )
    (comp (ref "R54")
      (value "470R")
      (footprint "eagle-import:0402")
      (libsource (lib "eagle-import") (part "R_0402"))
    )
    (comp (ref "R55")
      (value "470R")
      (footprint "eagle-import:0402")
      (libsource (lib "eagle-import") (part "R_0402"))
    )
    (comp (ref "R56")
      (value "470R")
      (footprint "eagle-import:0402")
      (libsource (lib "eagle-import") (part "R_0402"))
    )
    (comp (ref "R57")
      (value "470R")
      (footprint "eagle-import:0402")
      (libsource (lib "eagle-import") (part "R_0402"))
    )
    (comp (ref "R58")
      (value "470R")
      (footprint "eagle-import:0402")
      (libsource (lib "eagle-import") (part "R_0402"))
    )
    (comp (ref "R59")
      (value "470R")
      (footprint "eagle-import:0402")
      (libsource (lib "eagle-import") (part "R_0402"))
    )
    (comp (ref "R60")
      (value "470R")
      (footprint "eagle-import:0402")
      (libsource (lib "eagle-import") (part "R_0402"))
    )
    (comp (ref "R61")
      (value "470R")
      (footprint "eagle-import:0402")
      (libsource (lib "eagle-import") (part "R_0402"))
    )
    (comp (ref "R62")
      (value "470R")
      (footprint "eagle-import:0402")
      (libsource (lib "eagle-import") (part "R_0402"))
    )
    (comp (ref "R63")
      (value "470R")
      (footprint "eagle-import:0402")
      (libsource (lib "eagle-import") (part "R_0402"))
    )
    (comp (ref "R64")
      (value "470R")
      (footprint "eagle-import:0402")
      (libsource (lib "eagle-import") (part "R_0402"))
    )
    (comp (ref "R65")
      (value "470R")
      (footprint "eagle-import:0402")
      (libsource (lib "eagle-import") (part "R_0402"))
    )
    (comp (ref "R66")
      (value "470R")
      (footprint "eagle-import:0402")
      (libsource (lib "eagle-import") (part "R_0402"))
    )
    (comp (ref "R67")
      (value "470R")
      (footprint "eagle-import:0402")
      (libsource (lib "eagle-import") (part "R_0402"))
    )
    (comp (ref "R68")
      (value "470R")
      (footprint "eagle-import:0402")
      (libsource (lib "eagle-import") (part "R_0402"))
    )
    (comp (ref "R69")
      (value "470R")
      (footprint "eagle-import:0402")
      (libsource (lib "eagle-import") (part "R_0402"))
    )
    (comp (ref "R70")
      (value "470R")
      (footprint "eagle-import:0402")
      (libsource (lib "eagle-import") (part "R_0402"))
    )
    (comp (ref "R71")
      (value "470R")
      (footprint "eagle-import:0402")
      (libsource (lib "eagle-import") (part "R_0402"))
    )
    (comp (ref "R72")
      (value "4.99k")
      (footprint "eagle-import:0805")
      (libsource (lib "eagle-import") (part "R_0805"))
    )
    (comp (ref "R73")
      (value "470R")
      (footprint "eagle-import:0402")
      (libsource (lib "eagle-import") (part "R_0402"))
    )
    (comp (ref "R74")
      (value "10k")
      (footprint "eagle-import:0805")
      (libsource (lib "eagle-import") (part "R_0805"))
    )
    (comp (ref "R75")
      (value "470R")
      (footprint "eagle-import:0402")
      (libsource (lib "eagle-import") (part "R_0402"))
    )
    (comp (ref "R76")
      (value "470R")
      (footprint "eagle-import:0402")
      (libsource (lib "eagle-import") (part "R_0402"))
    )
    (comp (ref "R77")
      (value "470R")
      (footprint "eagle-import:0402")
      (libsource (lib "eagle-import") (part "R_0402"))
    )
    (comp (ref "R78")
      (value "4.99k")
      (footprint "eagle-import:0805")
      (libsource (lib "eagle-import") (part "R_0805"))
    )
    (comp (ref "R79")
      (value "470R")
      (footprint "eagle-import:0402")
      (libsource (lib "eagle-import") (part "R_0402"))
    )
    (comp (ref "R80")
      (value "470R")
      (footprint "eagle-import:0402")
      (libsource (lib "eagle-import") (part "R_0402"))
    )
    (comp (ref "R81")
      (value "470R")
      (footprint "eagle-import:0402")
      (libsource (lib "eagle-import") (part "R_0402"))
    )
    (comp (ref "R82")
      (value "10k")
      (footprint "eagle-import:0805")
      (libsource (lib "eagle-import") (part "R_0805"))
    )
    (comp (ref "R83")
      (value "470R")
      (footprint "eagle-import:0402")
      (libsource (lib "eagle-import") (part "R_0402"))
    )
    (comp (ref "R84")
      (value "470R")
      (footprint "eagle-import:0402")
      (libsource (lib "eagle-import") (part "R_0402"))
    )
    (comp (ref "R85")
      (value "470R")
      (footprint "eagle-import:0402")
      (libsource (lib "eagle-import") (part "R_0402"))
    )
    (comp (ref "R86")
      (value "4.99k")
      (footprint "eagle-import:0805")
      (libsource (lib "eagle-import") (part "R_0805"))
    )
    (comp (ref "R87")
      (value "470R")
      (footprint "eagle-import:0402")
      (libsource (lib "eagle-import") (part "R_0402"))
    )
    (comp (ref "R88")
      (value "10k")
      (footprint "eagle-import:0805")
      (libsource (lib "eagle-import") (part "R_0805"))
    )
    (comp (ref "R89")
      (value "470R")
      (footprint "eagle-import:0402")
      (libsource (lib "eagle-import") (part "R_0402"))
    )
    (comp (ref "R90")
      (value "4.99k")
      (footprint "eagle-import:0805")
      (libsource (lib "eagle-import") (part "R_0805"))
    )
    (comp (ref "R91")
      (value "470R")
      (footprint "eagle-import:0402")
      (libsource (lib "eagle-import") (part "R_0402"))
    )
    (comp (ref "R92")
      (value "10k")
      (footprint "eagle-import:0805")
      (libsource (lib "eagle-import") (part "R_0805"))
    )
    (comp (ref "R93")
      (value "470R")
      (footprint "eagle-import:0402")
      (libsource (lib "eagle-import") (part "R_0402"))
    )
    (comp (ref "R94")
      (value "4.99k")
      (footprint "eagle-import:0805")
      (libsource (lib "eagle-import") (part "R_0805"))
    )
    (comp (ref "R95")
      (value "470R")
      (footprint "eagle-import:0402")
      (libsource (lib "eagle-import") (part "R_0402"))
    )
    (comp (ref "R96")
      (value "10k")
      (footprint "eagle-import:0805")
      (libsource (lib "eagle-import") (part "R_0805"))
    )
    (comp (ref "R97")
      (value "470R")
      (footprint "eagle-import:0402")
      (libsource (lib "eagle-import") (part "R_0402"))
    )
    (comp (ref "R98")
      (value "10k")
      (footprint "eagle-import:0805")
      (libsource (lib "eagle-import") (part "R_0805"))
    )
    (comp (ref "R99")
      (value "470R")
      (footprint "eagle-import:0402")
      (libsource (lib "eagle-import") (part "R_0402"))
    )
    (comp (ref "R100")
      (value "10k")
      (footprint "eagle-import:0805")
      (libsource (lib "eagle-import") (part "R_0805"))
    )
    (comp (ref "R101")
      (value "4.99k")
      (footprint "eagle-import:0805")
      (libsource (lib "eagle-import") (part "R_0805"))
    )
    (comp (ref "R102")
      (value "4.99k")
      (footprint "eagle-import:0805")
      (libsource (lib "eagle-import") (part "R_0805"))
    )
    (comp (ref "R103")
      (value "4.99k")
      (footprint "eagle-import:0805")
      (libsource (lib "eagle-import") (part "R_0805"))
    )
    (comp (ref "RYS1")
      (value "1K")
      (footprint "eagle-import:0402")
      (libsource (lib "eagle-import") (part "R_0402"))
    )
    (comp (ref "RYS2")
      (value "1K")
      (footprint "eagle-import:0402")
      (libsource (lib "eagle-import") (part "R_0402"))
    )
    (comp (ref "RYS3")
      (value "1K")
      (footprint "eagle-import:0402")
      (libsource (lib "eagle-import") (part "R_0402"))
    )
    (comp (ref "RYS4")
      (value "1K")
      (footprint "eagle-import:0402")
      (libsource (lib "eagle-import") (part "R_0402"))
    )
    (comp (ref "RYS5")
      (value "1K")
      (footprint "eagle-import:0402")
      (libsource (lib "eagle-import") (part "R_0402"))
    )
    (comp (ref "RYS6")
      (value "1K")
      (footprint "eagle-import:0402")
      (libsource (lib "eagle-import") (part "R_0402"))
    )
    (comp (ref "RYS7")
      (value "1K")
      (footprint "eagle-import:0402")
      (libsource (lib "eagle-import") (part "R_0402"))
    )
    (comp (ref "RYS9")
      (value "1K")
      (footprint "eagle-import:0402")
      (libsource (lib "eagle-import") (part "R_0402"))
    )
    (comp (ref "RYS10")
      (value "1K")
      (footprint "eagle-import:0402")
      (libsource (lib "eagle-import") (part "R_0402"))
    )
    (comp (ref "RYS11")
      (value "1K")
      (footprint "eagle-import:0402")
      (libsource (lib "eagle-import") (part "R_0402"))
    )
    (comp (ref "RYS12")
      (value "1K")
      (footprint "eagle-import:0402")
      (libsource (lib "eagle-import") (part "R_0402"))
    )
    (comp (ref "RYS13")
      (value "1K")
      (footprint "eagle-import:0402")
      (libsource (lib "eagle-import") (part "R_0402"))
    )
    (comp (ref "RYS14")
      (value "1K")
      (footprint "eagle-import:0402")
      (libsource (lib "eagle-import") (part "R_0402"))
    )
    (comp (ref "RYS15")
      (value "1K")
      (footprint "eagle-import:0402")
      (libsource (lib "eagle-import") (part "R_0402"))
    )
    (comp (ref "RYS16")
      (value "1K")
      (footprint "eagle-import:0402")
      (libsource (lib "eagle-import") (part "R_0402"))
    )
    (comp (ref "RYS17")
      (value "1K")
      (footprint "eagle-import:0402")
      (libsource (lib "eagle-import") (part "R_0402"))
    )
    (comp (ref "RYS18")
      (value "1K")
      (footprint "eagle-import:0402")
      (libsource (lib "eagle-import") (part "R_0402"))
    )
    (comp (ref "RYS19")
      (value "1K")
      (footprint "eagle-import:0402")
      (libsource (lib "eagle-import") (part "R_0402"))
    )
    (comp (ref "RYS20")
      (value "1K")
      (footprint "eagle-import:0402")
      (libsource (lib "eagle-import") (part "R_0402"))
    )
    (comp (ref "RYS21")
      (value "1K")
      (footprint "eagle-import:0402")
      (libsource (lib "eagle-import") (part "R_0402"))
    )
    (comp (ref "RYS22")
      (value "1K")
      (footprint "eagle-import:0402")
      (libsource (lib "eagle-import") (part "R_0402"))
    )
    (comp (ref "RYS23")
      (value "1K")
      (footprint "eagle-import:0402")
      (libsource (lib "eagle-import") (part "R_0402"))
    )
    (comp (ref "RYS24")
      (value "1K")
      (footprint "eagle-import:0402")
      (libsource (lib "eagle-import") (part "R_0402"))
    )
    (comp (ref "RYS25")
      (value "1K")
      (footprint "eagle-import:0402")
      (libsource (lib "eagle-import") (part "R_0402"))
    )
    (comp (ref "RYS26")
      (value "1K")
      (footprint "eagle-import:0402")
      (libsource (lib "eagle-import") (part "R_0402"))
    )
    (comp (ref "RYS27")
      (value "1K")
      (footprint "eagle-import:0402")
      (libsource (lib "eagle-import") (part "R_0402"))
    )
    (comp (ref "RYS28")
      (value "1K")
      (footprint "eagle-import:0402")
      (libsource (lib "eagle-import") (part "R_0402"))
    )
    (comp (ref "RYS29")
      (value "1K")
      (footprint "eagle-import:0402")
      (libsource (lib "eagle-import") (part "R_0402"))
    )
    (comp (ref "RYS30")
      (value "1K")
      (footprint "eagle-import:0402")
      (libsource (lib "eagle-import") (part "R_0402"))
    )
    (comp (ref "RYS31")
      (value "1K")
      (footprint "eagle-import:0402")
      (libsource (lib "eagle-import") (part "R_0402"))
    )
    (comp (ref "RYS32")
      (value "1K")
      (footprint "eagle-import:0402")
      (libsource (lib "eagle-import") (part "R_0402"))
    )
    (comp (ref "RYS33")
      (value "1K")
      (footprint "eagle-import:0402")
      (libsource (lib "eagle-import") (part "R_0402"))
    )
    (comp (ref "RYS34")
      (value "1K")
      (footprint "eagle-import:0402")
      (libsource (lib "eagle-import") (part "R_0402"))
    )
    (comp (ref "RYS35")
      (value "1K")
      (footprint "eagle-import:0402")
      (libsource (lib "eagle-import") (part "R_0402"))
    )
    (comp (ref "RYS36")
      (value "1K")
      (footprint "eagle-import:0402")
      (libsource (lib "eagle-import") (part "R_0402"))
    )
    (comp (ref "RYS37")
      (value "1K")
      (footprint "eagle-import:0402")
      (libsource (lib "eagle-import") (part "R_0402"))
    )
    (comp (ref "RYS38")
      (value "1K")
      (footprint "eagle-import:0402")
      (libsource (lib "eagle-import") (part "R_0402"))
    )
    (comp (ref "RYS39")
      (value "1K")
      (footprint "eagle-import:0402")
      (libsource (lib "eagle-import") (part "R_0402"))
    )
    (comp (ref "RYS40")
      (value "1K")
      (footprint "eagle-import:0402")
      (libsource (lib "eagle-import") (part "R_0402"))
    )
    (comp (ref "RYS42")
      (value "1K")
      (footprint "eagle-import:0402")
      (libsource (lib "eagle-import") (part "R_0402"))
    )
    (comp (ref "RYS43")
      (value "1K")
      (footprint "eagle-import:0402")
      (libsource (lib "eagle-import") (part "R_0402"))
    )
    (comp (ref "RYS44")
      (value "1K")
      (footprint "eagle-import:0402")
      (libsource (lib "eagle-import") (part "R_0402"))
    )
    (comp (ref "RYS46")
      (value "1K")
      (footprint "eagle-import:0402")
      (libsource (lib "eagle-import") (part "R_0402"))
    )
    (comp (ref "RYS48")
      (value "1K")
      (footprint "eagle-import:0402")
      (libsource (lib "eagle-import") (part "R_0402"))
    )
    (comp (ref "RYS50")
      (value "1K")
      (footprint "eagle-import:0402")
      (libsource (lib "eagle-import") (part "R_0402"))
    )
    (comp (ref "RYS52")
      (value "1K")
      (footprint "eagle-import:0402")
      (libsource (lib "eagle-import") (part "R_0402"))
    )
    (comp (ref "RYS54")
      (value "1K")
      (footprint "eagle-import:0402")
      (libsource (lib "eagle-import") (part "R_0402"))
    )
    (comp (ref "RYS55")
      (value "1K")
      (footprint "eagle-import:0402")
      (libsource (lib "eagle-import") (part "R_0402"))
    )
    (comp (ref "RYS56")
      (value "1K")
      (footprint "eagle-import:0402")
      (libsource (lib "eagle-import") (part "R_0402"))
    )
    (comp (ref "RYS58")
      (value "1K")
      (footprint "eagle-import:0402")
      (libsource (lib "eagle-import") (part "R_0402"))
    )
    (comp (ref "RYS59")
      (value "1K")
      (footprint "eagle-import:0402")
      (libsource (lib "eagle-import") (part "R_0402"))
    )
    (comp (ref "RYS60")
      (value "1K")
      (footprint "eagle-import:0402")
      (libsource (lib "eagle-import") (part "R_0402"))
    )
    (comp (ref "RYS62")
      (value "1K")
      (footprint "eagle-import:0402")
      (libsource (lib "eagle-import") (part "R_0402"))
    )
    (comp (ref "RYS63")
      (value "1K")
      (footprint "eagle-import:0402")
      (libsource (lib "eagle-import") (part "R_0402"))
    )
    (comp (ref "RYS64")
      (value "1K")
      (footprint "eagle-import:0402")
      (libsource (lib "eagle-import") (part "R_0402"))
    )
    (comp (ref "RYS66")
      (value "1K")
      (footprint "eagle-import:0402")
      (libsource (lib "eagle-import") (part "R_0402"))
    )
    (comp (ref "RYS68")
      (value "1K")
      (footprint "eagle-import:0402")
      (libsource (lib "eagle-import") (part "R_0402"))
    )
    (comp (ref "RYS70")
      (value "1K")
      (footprint "eagle-import:0402")
      (libsource (lib "eagle-import") (part "R_0402"))
    )
    (comp (ref "RYS72")
      (value "1K")
      (footprint "eagle-import:0402")
      (libsource (lib "eagle-import") (part "R_0402"))
    )
    (comp (ref "RYS74")
      (value "1K")
      (footprint "eagle-import:0402")
      (libsource (lib "eagle-import") (part "R_0402"))
    )
    (comp (ref "RYS76")
      (value "1K")
      (footprint "eagle-import:0402")
      (libsource (lib "eagle-import") (part "R_0402"))
    )
    (comp (ref "RYS78")
      (value "1K")
      (footprint "eagle-import:0402")
      (libsource (lib "eagle-import") (part "R_0402"))
    )
    (comp (ref "SW1")
      (value "PTS810SJG250SMTRLFS")
      (footprint "eagle-import:PTS810")
      (fields (field (name "COPYRIGHT") "Copyright (C) 2018 Accelerated Designs. All rights reserved"))
      (libsource (lib "eagle-import") (part "PTS810SJG250SMTRLFS"))
    )
    (comp (ref "SW2")
      (value "PTS810SJG250SMTRLFS")
      (footprint "eagle-import:PTS810")
      (fields (field (name "COPYRIGHT") "Copyright (C) 2018 Accelerated Designs. All rights reserved"))
      (libsource (lib "eagle-import") (part "PTS810SJG250SMTRLFS"))
    )
    (comp (ref "SW3")
      (value "PTS810SJG250SMTRLFS")
      (footprint "eagle-import:PTS810")
      (fields (field (name "COPYRIGHT") "Copyright (C) 2018 Accelerated Designs. All rights reserved"))
      (libsource (lib "eagle-import") (part "PTS810SJG250SMTRLFS"))
    )
    (comp (ref "SW4")
      (value "PTS810SJG250SMTRLFS")
      (footprint "eagle-import:PTS810")
      (fields (field (name "COPYRIGHT") "Copyright (C) 2018 Accelerated Designs. All rights reserved"))
      (libsource (lib "eagle-import") (part "PTS810SJG250SMTRLFS"))
    )
    (comp (ref "U1")
      (value "BC846BW")
      (footprint "eagle-import:SOT323")
      (libsource (lib "eagle-import") (part "BC846BW"))
    )
    (comp (ref "U2")
      (value "BC846BW")
      (footprint "eagle-import:SOT323")
      (libsource (lib "eagle-import") (part "BC846BW"))
    )
    (comp (ref "U3")
      (value "BC846BW")
      (footprint "eagle-import:SOT323")
      (libsource (lib "eagle-import") (part "BC846BW"))
    )
    (comp (ref "U4")
      (value "BC846BW")
      (footprint "eagle-import:SOT323")
      (libsource (lib "eagle-import") (part "BC846BW"))
    )
    (comp (ref "U5")
      (value "BC846BW")
      (footprint "eagle-import:SOT323")
      (libsource (lib "eagle-import") (part "BC846BW"))
    )
    (comp (ref "U6")
      (value "BC846BW")
      (footprint "eagle-import:SOT323")
      (libsource (lib "eagle-import") (part "BC846BW"))
    )
    (comp (ref "U7")
      (value "BC846BW")
      (footprint "eagle-import:SOT323")
      (libsource (lib "eagle-import") (part "BC846BW"))
    )
    (comp (ref "U8")
      (value "BC846BW")
      (footprint "eagle-import:SOT323")
      (libsource (lib "eagle-import") (part "BC846BW"))
    )
    (comp (ref "U9")
      (value "BC846BW")
      (footprint "eagle-import:SOT323")
      (libsource (lib "eagle-import") (part "BC846BW"))
    )
    (comp (ref "U10")
      (value "BC846BW")
      (footprint "eagle-import:SOT323")
      (libsource (lib "eagle-import") (part "BC846BW"))
    )
    (comp (ref "U11")
      (value "BC846BW")
      (footprint "eagle-import:SOT323")
      (libsource (lib "eagle-import") (part "BC846BW"))
    )
    (comp (ref "U12")
      (value "BC846BW")
      (footprint "eagle-import:SOT323")
      (libsource (lib "eagle-import") (part "BC846BW"))
    )
    (comp (ref "U13")
      (value "BC846BW")
      (footprint "eagle-import:SOT323")
      (libsource (lib "eagle-import") (part "BC846BW"))
    )
    (comp (ref "U14")
      (value "BC846BW")
      (footprint "eagle-import:SOT323")
      (libsource (lib "eagle-import") (part "BC846BW"))
    )
    (comp (ref "U15")
      (value "BC846BW")
      (footprint "eagle-import:SOT323")
      (libsource (lib "eagle-import") (part "BC846BW"))
    )
    (comp (ref "U16")
      (value "BC846BW")
      (footprint "eagle-import:SOT323")
      (libsource (lib "eagle-import") (part "BC846BW"))
    )
    (comp (ref "U17")
      (value "BC846BW")
      (footprint "eagle-import:SOT323")
      (libsource (lib "eagle-import") (part "BC846BW"))
    )
    (comp (ref "U18")
      (value "BC846BW")
      (footprint "eagle-import:SOT323")
      (libsource (lib "eagle-import") (part "BC846BW"))
    )
    (comp (ref "U20")
      (value "BC846BW")
      (footprint "eagle-import:SOT323")
      (libsource (lib "eagle-import") (part "BC846BW"))
    )
    (comp (ref "U21")
      (value "BC846BW")
      (footprint "eagle-import:SOT323")
      (libsource (lib "eagle-import") (part "BC846BW"))
    )
    (comp (ref "U22")
      (value "BC846BW")
      (footprint "eagle-import:SOT323")
      (libsource (lib "eagle-import") (part "BC846BW"))
    )
    (comp (ref "U23")
      (value "BC846BW")
      (footprint "eagle-import:SOT323")
      (libsource (lib "eagle-import") (part "BC846BW"))
    )
    (comp (ref "U24")
      (value "BC846BW")
      (footprint "eagle-import:SOT323")
      (libsource (lib "eagle-import") (part "BC846BW"))
    )
    (comp (ref "U25")
      (value "BC846BW")
      (footprint "eagle-import:SOT323")
      (libsource (lib "eagle-import") (part "BC846BW"))
    )
    (comp (ref "U26")
      (value "BC846BW")
      (footprint "eagle-import:SOT323")
      (libsource (lib "eagle-import") (part "BC846BW"))
    )
    (comp (ref "U27")
      (value "BC846BW")
      (footprint "eagle-import:SOT323")
      (libsource (lib "eagle-import") (part "BC846BW"))
    )
    (comp (ref "U28")
      (value "BC846BW")
      (footprint "eagle-import:SOT323")
      (libsource (lib "eagle-import") (part "BC846BW"))
    )
    (comp (ref "U29")
      (value "BC846BW")
      (footprint "eagle-import:SOT323")
      (libsource (lib "eagle-import") (part "BC846BW"))
    )
    (comp (ref "U30")
      (value "BC846BW")
      (footprint "eagle-import:SOT323")
      (libsource (lib "eagle-import") (part "BC846BW"))
    )
    (comp (ref "U31")
      (value "BC846BW")
      (footprint "eagle-import:SOT323")
      (libsource (lib "eagle-import") (part "BC846BW"))
    )
    (comp (ref "U32")
      (value "BC846BW")
      (footprint "eagle-import:SOT323")
      (libsource (lib "eagle-import") (part "BC846BW"))
    )
    (comp (ref "U33")
      (value "BC846BW")
      (footprint "eagle-import:SOT323")
      (libsource (lib "eagle-import") (part "BC846BW"))
    )
    (comp (ref "U34")
      (value "BC846BW")
      (footprint "eagle-import:SOT323")
      (libsource (lib "eagle-import") (part "BC846BW"))
    )
    (comp (ref "U35")
      (value "BC846BW")
      (footprint "eagle-import:SOT323")
      (libsource (lib "eagle-import") (part "BC846BW"))
    )
    (comp (ref "U36")
      (value "BC846BW")
      (footprint "eagle-import:SOT323")
      (libsource (lib "eagle-import") (part "BC846BW"))
    )
    (comp (ref "U37")
      (value "BC846BW")
      (footprint "eagle-import:SOT323")
      (libsource (lib "eagle-import") (part "BC846BW"))
    )
    (comp (ref "U38")
      (value "BC846BW")
      (footprint "eagle-import:SOT323")
      (libsource (lib "eagle-import") (part "BC846BW"))
    )
    (comp (ref "U39")
      (value "BC846BW")
      (footprint "eagle-import:SOT323")
      (libsource (lib "eagle-import") (part "BC846BW"))
    )
    (comp (ref "U40")
      (value "BC846BW")
      (footprint "eagle-import:SOT323")
      (libsource (lib "eagle-import") (part "BC846BW"))
    )
    (comp (ref "U42")
      (value "BC846BW")
      (footprint "eagle-import:SOT323")
      (libsource (lib "eagle-import") (part "BC846BW"))
    )
    (comp (ref "U43")
      (value "BC846BW")
      (footprint "eagle-import:SOT323")
      (libsource (lib "eagle-import") (part "BC846BW"))
    )
    (comp (ref "U44")
      (value "BC846BW")
      (footprint "eagle-import:SOT323")
      (libsource (lib "eagle-import") (part "BC846BW"))
    )
    (comp (ref "U46")
      (value "BC846BW")
      (footprint "eagle-import:SOT323")
      (libsource (lib "eagle-import") (part "BC846BW"))
    )
    (comp (ref "U48")
      (value "BC846BW")
      (footprint "eagle-import:SOT323")
      (libsource (lib "eagle-import") (part "BC846BW"))
    )
    (comp (ref "U50")
      (value "BC846BW")
      (footprint "eagle-import:SOT323")
      (libsource (lib "eagle-import") (part "BC846BW"))
    )
    (comp (ref "U52")
      (value "BC846BW")
      (footprint "eagle-import:SOT323")
      (libsource (lib "eagle-import") (part "BC846BW"))
    )
    (comp (ref "U54")
      (value "BC846BW")
      (footprint "eagle-import:SOT323")
      (libsource (lib "eagle-import") (part "BC846BW"))
    )
    (comp (ref "U55")
      (value "BC846BW")
      (footprint "eagle-import:SOT323")
      (libsource (lib "eagle-import") (part "BC846BW"))
    )
    (comp (ref "U56")
      (value "BC846BW")
      (footprint "eagle-import:SOT323")
      (libsource (lib "eagle-import") (part "BC846BW"))
    )
    (comp (ref "U58")
      (value "BC846BW")
      (footprint "eagle-import:SOT323")
      (libsource (lib "eagle-import") (part "BC846BW"))
    )
    (comp (ref "U59")
      (value "BC846BW")
      (footprint "eagle-import:SOT323")
      (libsource (lib "eagle-import") (part "BC846BW"))
    )
    (comp (ref "U60")
      (value "BC846BW")
      (footprint "eagle-import:SOT323")
      (libsource (lib "eagle-import") (part "BC846BW"))
    )
    (comp (ref "U62")
      (value "BC846BW")
      (footprint "eagle-import:SOT323")
      (libsource (lib "eagle-import") (part "BC846BW"))
    )
    (comp (ref "U63")
      (value "BC846BW")
      (footprint "eagle-import:SOT323")
      (libsource (lib "eagle-import") (part "BC846BW"))
    )
    (comp (ref "U64")
      (value "BC846BW")
      (footprint "eagle-import:SOT323")
      (libsource (lib "eagle-import") (part "BC846BW"))
    )
    (comp (ref "U66")
      (value "BC846BW")
      (footprint "eagle-import:SOT323")
      (libsource (lib "eagle-import") (part "BC846BW"))
    )
    (comp (ref "U68")
      (value "BC846BW")
      (footprint "eagle-import:SOT323")
      (libsource (lib "eagle-import") (part "BC846BW"))
    )
    (comp (ref "U70")
      (value "BC846BW")
      (footprint "eagle-import:SOT323")
      (libsource (lib "eagle-import") (part "BC846BW"))
    )
    (comp (ref "U72")
      (value "BC846BW")
      (footprint "eagle-import:SOT323")
      (libsource (lib "eagle-import") (part "BC846BW"))
    )
    (comp (ref "U74")
      (value "BC846BW")
      (footprint "eagle-import:SOT323")
      (libsource (lib "eagle-import") (part "BC846BW"))
    )
    (comp (ref "U76")
      (value "BC846BW")
      (footprint "eagle-import:SOT323")
      (libsource (lib "eagle-import") (part "BC846BW"))
    )
    (comp (ref "U78")
      (value "BC846BW")
      (footprint "eagle-import:SOT323")
      (libsource (lib "eagle-import") (part "BC846BW"))
    )
  )
  (nets
    (net (code "1") (name "GND") (class "Default")
      (node (ref "J1") (pin "1") (pinfunction "1_1") (pintype "passive"))
      (node (ref "J1") (pin "2") (pinfunction "2_2") (pintype "passive"))
      (node (ref "LED18") (pin "C") (pinfunction "C_C") (pintype "passive"))
      (node (ref "LED19") (pin "C") (pinfunction "C_C") (pintype "passive"))
      (node (ref "LED20") (pin "C") (pinfunction "C_C") (pintype "passive"))
      (node (ref "LED21") (pin "C") (pinfunction "C_C") (pintype "passive"))
      (node (ref "LED3") (pin "C") (pinfunction "C_C") (pintype "passive"))
      (node (ref "R101") (pin "1") (pinfunction "1_1") (pintype "passive"))
      (node (ref "R102") (pin "1") (pinfunction "1_1") (pintype "passive"))
      (node (ref "R103") (pin "1") (pinfunction "1_1") (pintype "passive"))
      (node (ref "R72") (pin "1") (pinfunction "1_1") (pintype "passive"))
      (node (ref "R78") (pin "1") (pinfunction "1_1") (pintype "passive"))
      (node (ref "R86") (pin "1") (pinfunction "1_1") (pintype "passive"))
      (node (ref "R90") (pin "1") (pinfunction "1_1") (pintype "passive"))
      (node (ref "R94") (pin "1") (pinfunction "1_1") (pintype "passive"))
      (node (ref "U1") (pin "2") (pinfunction "E(1)_2") (pintype "output"))
      (node (ref "U10") (pin "2") (pinfunction "E(1)_2") (pintype "output"))
      (node (ref "U11") (pin "2") (pinfunction "E(1)_2") (pintype "output"))
      (node (ref "U12") (pin "2") (pinfunction "E(1)_2") (pintype "output"))
      (node (ref "U13") (pin "2") (pinfunction "E(1)_2") (pintype "output"))
      (node (ref "U14") (pin "2") (pinfunction "E(1)_2") (pintype "output"))
      (node (ref "U15") (pin "2") (pinfunction "E(1)_2") (pintype "output"))
      (node (ref "U16") (pin "2") (pinfunction "E(1)_2") (pintype "output"))
      (node (ref "U17") (pin "2") (pinfunction "E(1)_2") (pintype "output"))
      (node (ref "U18") (pin "2") (pinfunction "E(1)_2") (pintype "output"))
      (node (ref "U2") (pin "2") (pinfunction "E(1)_2") (pintype "output"))
      (node (ref "U20") (pin "2") (pinfunction "E(1)_2") (pintype "output"))
      (node (ref "U21") (pin "2") (pinfunction "E(1)_2") (pintype "output"))
      (node (ref "U22") (pin "2") (pinfunction "E(1)_2") (pintype "output"))
      (node (ref "U23") (pin "2") (pinfunction "E(1)_2") (pintype "output"))
      (node (ref "U24") (pin "2") (pinfunction "E(1)_2") (pintype "output"))
      (node (ref "U25") (pin "2") (pinfunction "E(1)_2") (pintype "output"))
      (node (ref "U26") (pin "2") (pinfunction "E(1)_2") (pintype "output"))
      (node (ref "U27") (pin "2") (pinfunction "E(1)_2") (pintype "output"))
      (node (ref "U28") (pin "2") (pinfunction "E(1)_2") (pintype "output"))
      (node (ref "U29") (pin "2") (pinfunction "E(1)_2") (pintype "output"))
      (node (ref "U3") (pin "2") (pinfunction "E(1)_2") (pintype "output"))
      (node (ref "U30") (pin "2") (pinfunction "E(1)_2") (pintype "output"))
      (node (ref "U31") (pin "2") (pinfunction "E(1)_2") (pintype "output"))
      (node (ref "U32") (pin "2") (pinfunction "E(1)_2") (pintype "output"))
      (node (ref "U33") (pin "2") (pinfunction "E(1)_2") (pintype "output"))
      (node (ref "U34") (pin "2") (pinfunction "E(1)_2") (pintype "output"))
      (node (ref "U35") (pin "2") (pinfunction "E(1)_2") (pintype "output"))
      (node (ref "U36") (pin "2") (pinfunction "E(1)_2") (pintype "output"))
      (node (ref "U37") (pin "2") (pinfunction "E(1)_2") (pintype "output"))
      (node (ref "U38") (pin "2") (pinfunction "E(1)_2") (pintype "output"))
      (node (ref "U39") (pin "2") (pinfunction "E(1)_2") (pintype "output"))
      (node (ref "U4") (pin "2") (pinfunction "E(1)_2") (pintype "output"))
      (node (ref "U40") (pin "2") (pinfunction "E(1)_2") (pintype "output"))
      (node (ref "U42") (pin "2") (pinfunction "E(1)_2") (pintype "output"))
      (node (ref "U43") (pin "2") (pinfunction "E(1)_2") (pintype "output"))
      (node (ref "U44") (pin "2") (pinfunction "E(1)_2") (pintype "output"))
      (node (ref "U46") (pin "2") (pinfunction "E(1)_2") (pintype "output"))
      (node (ref "U48") (pin "2") (pinfunction "E(1)_2") (pintype "output"))
      (node (ref "U5") (pin "2") (pinfunction "E(1)_2") (pintype "output"))
      (node (ref "U50") (pin "2") (pinfunction "E(1)_2") (pintype "output"))
      (node (ref "U52") (pin "2") (pinfunction "E(1)_2") (pintype "output"))
      (node (ref "U54") (pin "2") (pinfunction "E(1)_2") (pintype "output"))
      (node (ref "U55") (pin "2") (pinfunction "E(1)_2") (pintype "output"))
      (node (ref "U56") (pin "2") (pinfunction "E(1)_2") (pintype "output"))
      (node (ref "U58") (pin "2") (pinfunction "E(1)_2") (pintype "output"))
      (node (ref "U59") (pin "2") (pinfunction "E(1)_2") (pintype "output"))
      (node (ref "U6") (pin "2") (pinfunction "E(1)_2") (pintype "output"))
      (node (ref "U60") (pin "2") (pinfunction "E(1)_2") (pintype "output"))
      (node (ref "U62") (pin "2") (pinfunction "E(1)_2") (pintype "output"))
      (node (ref "U63") (pin "2") (pinfunction "E(1)_2") (pintype "output"))
      (node (ref "U64") (pin "2") (pinfunction "E(1)_2") (pintype "output"))
      (node (ref "U66") (pin "2") (pinfunction "E(1)_2") (pintype "output"))
      (node (ref "U68") (pin "2") (pinfunction "E(1)_2") (pintype "output"))
      (node (ref "U7") (pin "2") (pinfunction "E(1)_2") (pintype "output"))
      (node (ref "U70") (pin "2") (pinfunction "E(1)_2") (pintype "output"))
      (node (ref "U72") (pin "2") (pinfunction "E(1)_2") (pintype "output"))
      (node (ref "U74") (pin "2") (pinfunction "E(1)_2") (pintype "output"))
      (node (ref "U76") (pin "2") (pinfunction "E(1)_2") (pintype "output"))
      (node (ref "U78") (pin "2") (pinfunction "E(1)_2") (pintype "output"))
      (node (ref "U8") (pin "2") (pinfunction "E(1)_2") (pintype "output"))
      (node (ref "U9") (pin "2") (pinfunction "E(1)_2") (pintype "output"))
    )
    (net (code "2") (name "GNDE") (class "Default")
      (node (ref "J1") (pin "10") (pinfunction "10_10") (pintype "passive"))
      (node (ref "J1") (pin "9") (pinfunction "9_9") (pintype "passive"))
    )
    (net (code "3") (name "IIC_1_SCL") (class "Default")
      (node (ref "J10") (pin "P$5") (pinfunction "P$5_P$5") (pintype "bidirectional"))
      (node (ref "RYS44") (pin "P$1") (pinfunction "1_P$1") (pintype "passive"))
    )
    (net (code "4") (name "IIC_1_SDA") (class "Default")
      (node (ref "J10") (pin "P$6") (pinfunction "P$6_P$6") (pintype "bidirectional"))
      (node (ref "RYS3") (pin "P$1") (pinfunction "1_P$1") (pintype "passive"))
    )
    (net (code "5") (name "INT_MI_01") (class "Default")
      (node (ref "J10") (pin "P$39") (pinfunction "P$39_P$39") (pintype "bidirectional"))
      (node (ref "RYS78") (pin "P$1") (pinfunction "1_P$1") (pintype "passive"))
    )
    (net (code "6") (name "INT_MI_02") (class "Default")
      (node (ref "J10") (pin "P$40") (pinfunction "P$40_P$40") (pintype "bidirectional"))
      (node (ref "RYS38") (pin "P$1") (pinfunction "1_P$1") (pintype "passive"))
    )
    (net (code "7") (name "INT_MI_03") (class "Default")
      (node (ref "J10") (pin "P$9") (pinfunction "P$9_P$9") (pintype "bidirectional"))
      (node (ref "RYS48") (pin "P$1") (pinfunction "1_P$1") (pintype "passive"))
    )
    (net (code "8") (name "INT_MI_04") (class "Default")
      (node (ref "J10") (pin "P$10") (pinfunction "P$10_P$10") (pintype "bidirectional"))
      (node (ref "RYS7") (pin "P$1") (pinfunction "1_P$1") (pintype "passive"))
    )
    (net (code "9") (name "INT_MI_05") (class "Default")
      (node (ref "J10") (pin "P$1") (pinfunction "P$1_P$1") (pintype "bidirectional"))
      (node (ref "RYS40") (pin "P$1") (pinfunction "1_P$1") (pintype "passive"))
    )
    (net (code "10") (name "J2_1") (class "Default")
      (node (ref "J2") (pin "1") (pinfunction "1_1") (pintype "passive"))
      (node (ref "RYS35") (pin "P$1") (pinfunction "1_P$1") (pintype "passive"))
    )
    (net (code "11") (name "J2_2") (class "Default")
      (node (ref "J2") (pin "2") (pinfunction "2_2") (pintype "passive"))
      (node (ref "RYS55") (pin "P$1") (pinfunction "1_P$1") (pintype "passive"))
    )
    (net (code "12") (name "J2_3") (class "Default")
      (node (ref "J2") (pin "3") (pinfunction "3_3") (pintype "passive"))
      (node (ref "RYS39") (pin "P$1") (pinfunction "1_P$1") (pintype "passive"))
    )
    (net (code "13") (name "J2_4") (class "Default")
      (node (ref "J2") (pin "4") (pinfunction "4_4") (pintype "passive"))
      (node (ref "RYS59") (pin "P$1") (pinfunction "1_P$1") (pintype "passive"))
    )
    (net (code "14") (name "J2_5") (class "Default")
      (node (ref "J2") (pin "5") (pinfunction "5_5") (pintype "passive"))
      (node (ref "RYS43") (pin "P$1") (pinfunction "1_P$1") (pintype "passive"))
    )
    (net (code "15") (name "J2_6") (class "Default")
      (node (ref "J2") (pin "6") (pinfunction "6_6") (pintype "passive"))
      (node (ref "RYS63") (pin "P$1") (pinfunction "1_P$1") (pintype "passive"))
    )
    (net (code "16") (name "J2_7") (class "Default")
      (node (ref "J2") (pin "7") (pinfunction "7_7") (pintype "passive"))
      (node (ref "R74") (pin "1") (pinfunction "1_1") (pintype "passive"))
      (node (ref "R78") (pin "2") (pinfunction "2_2") (pintype "passive"))
    )
    (net (code "17") (name "J2_8") (class "Default")
      (node (ref "J2") (pin "8") (pinfunction "8_8") (pintype "passive"))
      (node (ref "R26") (pin "1") (pinfunction "1_1") (pintype "passive"))
      (node (ref "R72") (pin "2") (pinfunction "2_2") (pintype "passive"))
    )
    (net (code "18") (name "J2_9") (class "Default")
      (node (ref "J2") (pin "9") (pinfunction "9_9") (pintype "passive"))
      (node (ref "R88") (pin "1") (pinfunction "1_1") (pintype "passive"))
      (node (ref "R90") (pin "2") (pinfunction "2_2") (pintype "passive"))
    )
    (net (code "19") (name "J2_10") (class "Default")
      (node (ref "J2") (pin "10") (pinfunction "10_10") (pintype "passive"))
      (node (ref "R82") (pin "1") (pinfunction "1_1") (pintype "passive"))
      (node (ref "R86") (pin "2") (pinfunction "2_2") (pintype "passive"))
    )
    (net (code "20") (name "J3_1") (class "Default")
      (node (ref "J3") (pin "1") (pinfunction "1_1") (pintype "passive"))
      (node (ref "R102") (pin "2") (pinfunction "2_2") (pintype "passive"))
      (node (ref "R98") (pin "1") (pinfunction "1_1") (pintype "passive"))
    )
    (net (code "21") (name "J3_2") (class "Default")
      (node (ref "J3") (pin "2") (pinfunction "2_2") (pintype "passive"))
      (node (ref "R100") (pin "1") (pinfunction "1_1") (pintype "passive"))
      (node (ref "R103") (pin "2") (pinfunction "2_2") (pintype "passive"))
    )
    (net (code "22") (name "J3_3") (class "Default")
      (node (ref "J3") (pin "3") (pinfunction "3_3") (pintype "passive"))
      (node (ref "R101") (pin "2") (pinfunction "2_2") (pintype "passive"))
      (node (ref "R96") (pin "1") (pinfunction "1_1") (pintype "passive"))
    )
    (net (code "23") (name "J3_4") (class "Default")
      (node (ref "J3") (pin "4") (pinfunction "4_4") (pintype "passive"))
      (node (ref "R92") (pin "1") (pinfunction "1_1") (pintype "passive"))
      (node (ref "R94") (pin "2") (pinfunction "2_2") (pintype "passive"))
    )
    (net (code "24") (name "J3_5") (class "Default")
      (node (ref "J3") (pin "5") (pinfunction "5_5") (pintype "passive"))
      (node (ref "RYS11") (pin "P$1") (pinfunction "1_P$1") (pintype "passive"))
    )
    (net (code "25") (name "J3_6") (class "Default")
      (node (ref "J3") (pin "6") (pinfunction "6_6") (pintype "passive"))
      (node (ref "RYS23") (pin "P$1") (pinfunction "1_P$1") (pintype "passive"))
    )
    (net (code "26") (name "J3_7") (class "Default")
      (node (ref "J3") (pin "7") (pinfunction "7_7") (pintype "passive"))
      (node (ref "RYS19") (pin "P$1") (pinfunction "1_P$1") (pintype "passive"))
    )
    (net (code "27") (name "J3_8") (class "Default")
      (node (ref "J3") (pin "8") (pinfunction "8_8") (pintype "passive"))
      (node (ref "RYS27") (pin "P$1") (pinfunction "1_P$1") (pintype "passive"))
    )
    (net (code "28") (name "J3_9") (class "Default")
      (node (ref "J3") (pin "9") (pinfunction "9_9") (pintype "passive"))
      (node (ref "RYS15") (pin "P$1") (pinfunction "1_P$1") (pintype "passive"))
    )
    (net (code "29") (name "J3_10") (class "Default")
      (node (ref "J3") (pin "10") (pinfunction "10_10") (pintype "passive"))
      (node (ref "RYS31") (pin "P$1") (pinfunction "1_P$1") (pintype "passive"))
    )
    (net (code "30") (name "J4_1") (class "Default")
      (node (ref "J4") (pin "1") (pinfunction "1_1") (pintype "passive"))
      (node (ref "RYS37") (pin "P$1") (pinfunction "1_P$1") (pintype "passive"))
    )
    (net (code "31") (name "J4_2") (class "Default")
      (node (ref "J4") (pin "2") (pinfunction "2_2") (pintype "passive"))
      (node (ref "RYS33") (pin "P$1") (pinfunction "1_P$1") (pintype "passive"))
    )
    (net (code "32") (name "J4_3") (class "Default")
      (node (ref "J4") (pin "3") (pinfunction "3_3") (pintype "passive"))
      (node (ref "RYS29") (pin "P$1") (pinfunction "1_P$1") (pintype "passive"))
    )
    (net (code "33") (name "J4_4") (class "Default")
      (node (ref "J4") (pin "4") (pinfunction "4_4") (pintype "passive"))
      (node (ref "RYS25") (pin "P$1") (pinfunction "1_P$1") (pintype "passive"))
    )
    (net (code "34") (name "J4_5") (class "Default")
      (node (ref "J4") (pin "5") (pinfunction "5_5") (pintype "passive"))
      (node (ref "RYS21") (pin "P$1") (pinfunction "1_P$1") (pintype "passive"))
    )
    (net (code "35") (name "J4_6") (class "Default")
      (node (ref "J4") (pin "6") (pinfunction "6_6") (pintype "passive"))
      (node (ref "RYS17") (pin "P$1") (pinfunction "1_P$1") (pintype "passive"))
    )
    (net (code "36") (name "J4_7") (class "Default")
      (node (ref "J4") (pin "7") (pinfunction "7_7") (pintype "passive"))
      (node (ref "RYS9") (pin "P$1") (pinfunction "1_P$1") (pintype "passive"))
    )
    (net (code "37") (name "J4_8") (class "Default")
      (node (ref "J4") (pin "8") (pinfunction "8_8") (pintype "passive"))
      (node (ref "RYS6") (pin "P$1") (pinfunction "1_P$1") (pintype "passive"))
    )
    (net (code "38") (name "J4_9") (class "Default")
      (node (ref "J4") (pin "9") (pinfunction "9_9") (pintype "passive"))
      (node (ref "RYS13") (pin "P$1") (pinfunction "1_P$1") (pintype "passive"))
    )
    (net (code "39") (name "J4_10") (class "Default")
      (node (ref "J4") (pin "10") (pinfunction "10_10") (pintype "passive"))
      (node (ref "RYS4") (pin "P$1") (pinfunction "1_P$1") (pintype "passive"))
    )
    (net (code "40") (name "Net-(J5-PadP$1)") (class "Default")
      (node (ref "J5") (pin "P$1") (pinfunction "P$1_P$1") (pintype "bidirectional"))
      (node (ref "LED6") (pin "C") (pinfunction "C_C") (pintype "passive"))
    )
    (net (code "41") (name "Net-(J5-PadP$2)") (class "Default")
      (node (ref "J5") (pin "P$2") (pinfunction "P$2_P$2") (pintype "bidirectional"))
      (node (ref "LED7") (pin "C") (pinfunction "C_C") (pintype "passive"))
    )
    (net (code "42") (name "Net-(J5-PadP$3)") (class "Default")
      (node (ref "J5") (pin "P$3") (pinfunction "P$3_P$3") (pintype "bidirectional"))
      (node (ref "LED8") (pin "C") (pinfunction "C_C") (pintype "passive"))
    )
    (net (code "43") (name "Net-(J5-PadP$4)") (class "Default")
      (node (ref "J5") (pin "P$4") (pinfunction "P$4_P$4") (pintype "bidirectional"))
      (node (ref "LED9") (pin "C") (pinfunction "C_C") (pintype "passive"))
    )
    (net (code "44") (name "Net-(J6-PadP$1)") (class "Default")
      (node (ref "J6") (pin "P$1") (pinfunction "P$1_P$1") (pintype "bidirectional"))
      (node (ref "LED1") (pin "C") (pinfunction "C_C") (pintype "passive"))
    )
    (net (code "45") (name "Net-(J6-PadP$2)") (class "Default")
      (node (ref "J6") (pin "P$2") (pinfunction "P$2_P$2") (pintype "bidirectional"))
      (node (ref "LED2") (pin "C") (pinfunction "C_C") (pintype "passive"))
    )
    (net (code "46") (name "Net-(J6-PadP$3)") (class "Default")
      (node (ref "J6") (pin "P$3") (pinfunction "P$3_P$3") (pintype "bidirectional"))
      (node (ref "LED4") (pin "C") (pinfunction "C_C") (pintype "passive"))
    )
    (net (code "47") (name "Net-(J6-PadP$4)") (class "Default")
      (node (ref "J6") (pin "P$4") (pinfunction "P$4_P$4") (pintype "bidirectional"))
      (node (ref "LED5") (pin "C") (pinfunction "C_C") (pintype "passive"))
    )
    (net (code "48") (name "Net-(J13-PadP$1)") (class "Default")
      (node (ref "J13") (pin "P$1") (pinfunction "P$1_P$1") (pintype "bidirectional"))
      (node (ref "LED10") (pin "C") (pinfunction "C_C") (pintype "passive"))
    )
    (net (code "49") (name "Net-(J13-PadP$2)") (class "Default")
      (node (ref "J13") (pin "P$2") (pinfunction "P$2_P$2") (pintype "bidirectional"))
      (node (ref "LED11") (pin "C") (pinfunction "C_C") (pintype "passive"))
    )
    (net (code "50") (name "Net-(J13-PadP$3)") (class "Default")
      (node (ref "J13") (pin "P$3") (pinfunction "P$3_P$3") (pintype "bidirectional"))
      (node (ref "LED12") (pin "C") (pinfunction "C_C") (pintype "passive"))
    )
    (net (code "51") (name "Net-(J13-PadP$4)") (class "Default")
      (node (ref "J13") (pin "P$4") (pinfunction "P$4_P$4") (pintype "bidirectional"))
      (node (ref "LED13") (pin "C") (pinfunction "C_C") (pintype "passive"))
    )
    (net (code "52") (name "Net-(J14-PadP$1)") (class "Default")
      (node (ref "J14") (pin "P$1") (pinfunction "P$1_P$1") (pintype "bidirectional"))
      (node (ref "LED14") (pin "C") (pinfunction "C_C") (pintype "passive"))
    )
    (net (code "53") (name "Net-(J14-PadP$2)") (class "Default")
      (node (ref "J14") (pin "P$2") (pinfunction "P$2_P$2") (pintype "bidirectional"))
      (node (ref "LED15") (pin "C") (pinfunction "C_C") (pintype "passive"))
    )
    (net (code "54") (name "Net-(J14-PadP$3)") (class "Default")
      (node (ref "J14") (pin "P$3") (pinfunction "P$3_P$3") (pintype "bidirectional"))
      (node (ref "LED16") (pin "C") (pinfunction "C_C") (pintype "passive"))
    )
    (net (code "55") (name "Net-(J14-PadP$4)") (class "Default")
      (node (ref "J14") (pin "P$4") (pinfunction "P$4_P$4") (pintype "bidirectional"))
      (node (ref "LED17") (pin "C") (pinfunction "C_C") (pintype "passive"))
    )
    (net (code "56") (name "Net-(R1-2)") (class "Default")
      (node (ref "LED1") (pin "A") (pinfunction "A_A") (pintype "passive"))
      (node (ref "R1") (pin "P$2") (pinfunction "2_P$2") (pintype "passive"))
    )
    (net (code "57") (name "Net-(R2-2)") (class "Default")
      (node (ref "LED2") (pin "A") (pinfunction "A_A") (pintype "passive"))
      (node (ref "R2") (pin "P$2") (pinfunction "2_P$2") (pintype "passive"))
    )
    (net (code "58") (name "Net-(R3-2)") (class "Default")
      (node (ref "LED4") (pin "A") (pinfunction "A_A") (pintype "passive"))
      (node (ref "R3") (pin "P$2") (pinfunction "2_P$2") (pintype "passive"))
    )
    (net (code "59") (name "Net-(R4-2)") (class "Default")
      (node (ref "LED5") (pin "A") (pinfunction "A_A") (pintype "passive"))
      (node (ref "R4") (pin "P$2") (pinfunction "2_P$2") (pintype "passive"))
    )
    (net (code "60") (name "Net-(R5-2)") (class "Default")
      (node (ref "LED6") (pin "A") (pinfunction "A_A") (pintype "passive"))
      (node (ref "R5") (pin "P$2") (pinfunction "2_P$2") (pintype "passive"))
    )
    (net (code "61") (name "Net-(R6-2)") (class "Default")
      (node (ref "LED7") (pin "A") (pinfunction "A_A") (pintype "passive"))
      (node (ref "R6") (pin "P$2") (pinfunction "2_P$2") (pintype "passive"))
    )
    (net (code "62") (name "Net-(R7-2)") (class "Default")
      (node (ref "LED8") (pin "A") (pinfunction "A_A") (pintype "passive"))
      (node (ref "R7") (pin "P$2") (pinfunction "2_P$2") (pintype "passive"))
    )
    (net (code "63") (name "Net-(R8-2)") (class "Default")
      (node (ref "LED9") (pin "A") (pinfunction "A_A") (pintype "passive"))
      (node (ref "R8") (pin "P$2") (pinfunction "2_P$2") (pintype "passive"))
    )
    (net (code "64") (name "Net-(R9-2)") (class "Default")
      (node (ref "LED10") (pin "A") (pinfunction "A_A") (pintype "passive"))
      (node (ref "R9") (pin "P$2") (pinfunction "2_P$2") (pintype "passive"))
    )
    (net (code "65") (name "Net-(R10-2)") (class "Default")
      (node (ref "LED11") (pin "A") (pinfunction "A_A") (pintype "passive"))
      (node (ref "R10") (pin "P$2") (pinfunction "2_P$2") (pintype "passive"))
    )
    (net (code "66") (name "Net-(R11-2)") (class "Default")
      (node (ref "LED12") (pin "A") (pinfunction "A_A") (pintype "passive"))
      (node (ref "R11") (pin "P$2") (pinfunction "2_P$2") (pintype "passive"))
    )
    (net (code "67") (name "Net-(R12-2)") (class "Default")
      (node (ref "LED13") (pin "A") (pinfunction "A_A") (pintype "passive"))
      (node (ref "R12") (pin "P$2") (pinfunction "2_P$2") (pintype "passive"))
    )
    (net (code "68") (name "Net-(R13-1)") (class "Default")
      (node (ref "LED3") (pin "A") (pinfunction "A_A") (pintype "passive"))
      (node (ref "R13") (pin "P$1") (pinfunction "1_P$1") (pintype "passive"))
    )
    (net (code "69") (name "Net-(R14-2)") (class "Default")
      (node (ref "LED14") (pin "A") (pinfunction "A_A") (pintype "passive"))
      (node (ref "R14") (pin "P$2") (pinfunction "2_P$2") (pintype "passive"))
    )
    (net (code "70") (name "Net-(R15-2)") (class "Default")
      (node (ref "LED15") (pin "A") (pinfunction "A_A") (pintype "passive"))
      (node (ref "R15") (pin "P$2") (pinfunction "2_P$2") (pintype "passive"))
    )
    (net (code "71") (name "Net-(R16-2)") (class "Default")
      (node (ref "LED16") (pin "A") (pinfunction "A_A") (pintype "passive"))
      (node (ref "R16") (pin "P$2") (pinfunction "2_P$2") (pintype "passive"))
    )
    (net (code "72") (name "Net-(R17-2)") (class "Default")
      (node (ref "LED17") (pin "A") (pinfunction "A_A") (pintype "passive"))
      (node (ref "R17") (pin "P$2") (pinfunction "2_P$2") (pintype "passive"))
    )
    (net (code "73") (name "Net-(R18-1)") (class "Default")
      (node (ref "LED18") (pin "A") (pinfunction "A_A") (pintype "passive"))
      (node (ref "R18") (pin "P$1") (pinfunction "1_P$1") (pintype "passive"))
    )
    (net (code "74") (name "Net-(R18-2)") (class "Default")
      (node (ref "R18") (pin "P$2") (pinfunction "2_P$2") (pintype "passive"))
      (node (ref "R22") (pin "P$2") (pinfunction "2_P$2") (pintype "passive"))
      (node (ref "SW1") (pin "3") (pinfunction "3_3") (pintype "passive"))
      (node (ref "SW1") (pin "4") (pinfunction "4_4") (pintype "passive"))
    )
    (net (code "75") (name "Net-(R19-1)") (class "Default")
      (node (ref "LED19") (pin "A") (pinfunction "A_A") (pintype "passive"))
      (node (ref "R19") (pin "P$1") (pinfunction "1_P$1") (pintype "passive"))
    )
    (net (code "76") (name "Net-(R19-2)") (class "Default")
      (node (ref "R19") (pin "P$2") (pinfunction "2_P$2") (pintype "passive"))
      (node (ref "R34") (pin "P$2") (pinfunction "2_P$2") (pintype "passive"))
      (node (ref "SW2") (pin "3") (pinfunction "3_3") (pintype "passive"))
      (node (ref "SW2") (pin "4") (pinfunction "4_4") (pintype "passive"))
    )
    (net (code "77") (name "Net-(R20-1)") (class "Default")
      (node (ref "LED20") (pin "A") (pinfunction "A_A") (pintype "passive"))
      (node (ref "R20") (pin "P$1") (pinfunction "1_P$1") (pintype "passive"))
    )
    (net (code "78") (name "Net-(R20-2)") (class "Default")
      (node (ref "R20") (pin "P$2") (pinfunction "2_P$2") (pintype "passive"))
      (node (ref "R42") (pin "P$2") (pinfunction "2_P$2") (pintype "passive"))
      (node (ref "SW3") (pin "3") (pinfunction "3_3") (pintype "passive"))
      (node (ref "SW3") (pin "4") (pinfunction "4_4") (pintype "passive"))
    )
    (net (code "79") (name "Net-(R21-1)") (class "Default")
      (node (ref "LED21") (pin "A") (pinfunction "A_A") (pintype "passive"))
      (node (ref "R21") (pin "P$1") (pinfunction "1_P$1") (pintype "passive"))
    )
    (net (code "80") (name "Net-(R21-2)") (class "Default")
      (node (ref "R21") (pin "P$2") (pinfunction "2_P$2") (pintype "passive"))
      (node (ref "R46") (pin "P$2") (pinfunction "2_P$2") (pintype "passive"))
      (node (ref "SW4") (pin "3") (pinfunction "3_3") (pintype "passive"))
      (node (ref "SW4") (pin "4") (pinfunction "4_4") (pintype "passive"))
    )
    (net (code "81") (name "Net-(R22-1)") (class "Default")
      (node (ref "J15") (pin "P$1") (pinfunction "P$1_P$1") (pintype "bidirectional"))
      (node (ref "R22") (pin "P$1") (pinfunction "1_P$1") (pintype "passive"))
    )
    (net (code "82") (name "Net-(R23-1)") (class "Default")
      (node (ref "LED23") (pin "A") (pinfunction "A_A") (pintype "passive"))
      (node (ref "R23") (pin "P$1") (pinfunction "1_P$1") (pintype "passive"))
    )
    (net (code "83") (name "Net-(R24-1)") (class "Default")
      (node (ref "LED24") (pin "A") (pinfunction "A_A") (pintype "passive"))
      (node (ref "R24") (pin "P$1") (pinfunction "1_P$1") (pintype "passive"))
    )
    (net (code "84") (name "Net-(R25-1)") (class "Default")
      (node (ref "LED25") (pin "A") (pinfunction "A_A") (pintype "passive"))
      (node (ref "R25") (pin "P$1") (pinfunction "1_P$1") (pintype "passive"))
    )
    (net (code "85") (name "Net-(R27-1)") (class "Default")
      (node (ref "LED27") (pin "A") (pinfunction "A_A") (pintype "passive"))
      (node (ref "R27") (pin "P$1") (pinfunction "1_P$1") (pintype "passive"))
    )
    (net (code "86") (name "Net-(R28-1)") (class "Default")
      (node (ref "LED26") (pin "A") (pinfunction "A_A") (pintype "passive"))
      (node (ref "R28") (pin "P$1") (pinfunction "1_P$1") (pintype "passive"))
    )
    (net (code "87") (name "Net-(R29-1)") (class "Default")
      (node (ref "LED29") (pin "A") (pinfunction "A_A") (pintype "passive"))
      (node (ref "R29") (pin "P$1") (pinfunction "1_P$1") (pintype "passive"))
    )
    (net (code "88") (name "Net-(R30-1)") (class "Default")
      (node (ref "LED28") (pin "A") (pinfunction "A_A") (pintype "passive"))
      (node (ref "R30") (pin "P$1") (pinfunction "1_P$1") (pintype "passive"))
    )
    (net (code "89") (name "Net-(R31-1)") (class "Default")
      (node (ref "LED31") (pin "A") (pinfunction "A_A") (pintype "passive"))
      (node (ref "R31") (pin "P$1") (pinfunction "1_P$1") (pintype "passive"))
    )
    (net (code "90") (name "Net-(R32-1)") (class "Default")
      (node (ref "LED32") (pin "A") (pinfunction "A_A") (pintype "passive"))
      (node (ref "R32") (pin "P$1") (pinfunction "1_P$1") (pintype "passive"))
    )
    (net (code "91") (name "Net-(R33-1)") (class "Default")
      (node (ref "LED33") (pin "A") (pinfunction "A_A") (pintype "passive"))
      (node (ref "R33") (pin "P$1") (pinfunction "1_P$1") (pintype "passive"))
    )
    (net (code "92") (name "Net-(R34-1)") (class "Default")
      (node (ref "J15") (pin "P$2") (pinfunction "P$2_P$2") (pintype "bidirectional"))
      (node (ref "R34") (pin "P$1") (pinfunction "1_P$1") (pintype "passive"))
    )
    (net (code "93") (name "Net-(R35-1)") (class "Default")
      (node (ref "LED35") (pin "A") (pinfunction "A_A") (pintype "passive"))
      (node (ref "R35") (pin "P$1") (pinfunction "1_P$1") (pintype "passive"))
    )
    (net (code "94") (name "Net-(R36-1)") (class "Default")
      (node (ref "LED36") (pin "A") (pinfunction "A_A") (pintype "passive"))
      (node (ref "R36") (pin "P$1") (pinfunction "1_P$1") (pintype "passive"))
    )
    (net (code "95") (name "Net-(R37-1)") (class "Default")
      (node (ref "LED37") (pin "A") (pinfunction "A_A") (pintype "passive"))
      (node (ref "R37") (pin "P$1") (pinfunction "1_P$1") (pintype "passive"))
    )
    (net (code "96") (name "Net-(R38-1)") (class "Default")
      (node (ref "LED30") (pin "A") (pinfunction "A_A") (pintype "passive"))
      (node (ref "R38") (pin "P$1") (pinfunction "1_P$1") (pintype "passive"))
    )
    (net (code "97") (name "Net-(R39-1)") (class "Default")
      (node (ref "LED39") (pin "A") (pinfunction "A_A") (pintype "passive"))
      (node (ref "R39") (pin "P$1") (pinfunction "1_P$1") (pintype "passive"))
    )
    (net (code "98") (name "Net-(R40-1)") (class "Default")
      (node (ref "LED40") (pin "A") (pinfunction "A_A") (pintype "passive"))
      (node (ref "R40") (pin "P$1") (pinfunction "1_P$1") (pintype "passive"))
    )
    (net (code "99") (name "Net-(R41-1)") (class "Default")
      (node (ref "LED41") (pin "A") (pinfunction "A_A") (pintype "passive"))
      (node (ref "R41") (pin "P$1") (pinfunction "1_P$1") (pintype "passive"))
    )
    (net (code "100") (name "Net-(R42-1)") (class "Default")
      (node (ref "J15") (pin "P$3") (pinfunction "P$3_P$3") (pintype "bidirectional"))
      (node (ref "R42") (pin "P$1") (pinfunction "1_P$1") (pintype "passive"))
    )
    (net (code "101") (name "Net-(R43-1)") (class "Default")
      (node (ref "LED43") (pin "A") (pinfunction "A_A") (pintype "passive"))
      (node (ref "R43") (pin "P$1") (pinfunction "1_P$1") (pintype "passive"))
    )
    (net (code "102") (name "Net-(R44-1)") (class "Default")
      (node (ref "LED44") (pin "A") (pinfunction "A_A") (pintype "passive"))
      (node (ref "R44") (pin "P$1") (pinfunction "1_P$1") (pintype "passive"))
    )
    (net (code "103") (name "Net-(R45-1)") (class "Default")
      (node (ref "LED45") (pin "A") (pinfunction "A_A") (pintype "passive"))
      (node (ref "R45") (pin "P$1") (pinfunction "1_P$1") (pintype "passive"))
    )
    (net (code "104") (name "Net-(R46-1)") (class "Default")
      (node (ref "J15") (pin "P$4") (pinfunction "P$4_P$4") (pintype "bidirectional"))
      (node (ref "R46") (pin "P$1") (pinfunction "1_P$1") (pintype "passive"))
    )
    (net (code "105") (name "Net-(R47-1)") (class "Default")
      (node (ref "LED47") (pin "A") (pinfunction "A_A") (pintype "passive"))
      (node (ref "R47") (pin "P$1") (pinfunction "1_P$1") (pintype "passive"))
    )
    (net (code "106") (name "Net-(R48-1)") (class "Default")
      (node (ref "LED48") (pin "A") (pinfunction "A_A") (pintype "passive"))
      (node (ref "R48") (pin "P$1") (pinfunction "1_P$1") (pintype "passive"))
    )
    (net (code "107") (name "Net-(R49-1)") (class "Default")
      (node (ref "LED49") (pin "A") (pinfunction "A_A") (pintype "passive"))
      (node (ref "R49") (pin "P$1") (pinfunction "1_P$1") (pintype "passive"))
    )
    (net (code "108") (name "Net-(R50-1)") (class "Default")
      (node (ref "LED34") (pin "A") (pinfunction "A_A") (pintype "passive"))
      (node (ref "R50") (pin "P$1") (pinfunction "1_P$1") (pintype "passive"))
    )
    (net (code "109") (name "Net-(R51-1)") (class "Default")
      (node (ref "LED51") (pin "A") (pinfunction "A_A") (pintype "passive"))
      (node (ref "R51") (pin "P$1") (pinfunction "1_P$1") (pintype "passive"))
    )
    (net (code "110") (name "Net-(R52-1)") (class "Default")
      (node (ref "LED52") (pin "A") (pinfunction "A_A") (pintype "passive"))
      (node (ref "R52") (pin "P$1") (pinfunction "1_P$1") (pintype "passive"))
    )
    (net (code "111") (name "Net-(R53-1)") (class "Default")
      (node (ref "LED53") (pin "A") (pinfunction "A_A") (pintype "passive"))
      (node (ref "R53") (pin "P$1") (pinfunction "1_P$1") (pintype "passive"))
    )
    (net (code "112") (name "Net-(R54-1)") (class "Default")
      (node (ref "LED38") (pin "A") (pinfunction "A_A") (pintype "passive"))
      (node (ref "R54") (pin "P$1") (pinfunction "1_P$1") (pintype "passive"))
    )
    (net (code "113") (name "Net-(R55-1)") (class "Default")
      (node (ref "LED55") (pin "A") (pinfunction "A_A") (pintype "passive"))
      (node (ref "R55") (pin "P$1") (pinfunction "1_P$1") (pintype "passive"))
    )
    (net (code "114") (name "Net-(R56-1)") (class "Default")
      (node (ref "LED56") (pin "A") (pinfunction "A_A") (pintype "passive"))
      (node (ref "R56") (pin "P$1") (pinfunction "1_P$1") (pintype "passive"))
    )
    (net (code "115") (name "Net-(R57-1)") (class "Default")
      (node (ref "LED57") (pin "A") (pinfunction "A_A") (pintype "passive"))
      (node (ref "R57") (pin "P$1") (pinfunction "1_P$1") (pintype "passive"))
    )
    (net (code "116") (name "Net-(R58-1)") (class "Default")
      (node (ref "LED42") (pin "A") (pinfunction "A_A") (pintype "passive"))
      (node (ref "R58") (pin "P$1") (pinfunction "1_P$1") (pintype "passive"))
    )
    (net (code "117") (name "Net-(R59-1)") (class "Default")
      (node (ref "LED59") (pin "A") (pinfunction "A_A") (pintype "passive"))
      (node (ref "R59") (pin "P$1") (pinfunction "1_P$1") (pintype "passive"))
    )
    (net (code "118") (name "Net-(R60-1)") (class "Default")
      (node (ref "LED60") (pin "A") (pinfunction "A_A") (pintype "passive"))
      (node (ref "R60") (pin "P$1") (pinfunction "1_P$1") (pintype "passive"))
    )
    (net (code "119") (name "Net-(R61-1)") (class "Default")
      (node (ref "LED61") (pin "A") (pinfunction "A_A") (pintype "passive"))
      (node (ref "R61") (pin "P$1") (pinfunction "1_P$1") (pintype "passive"))
    )
    (net (code "120") (name "Net-(R62-1)") (class "Default")
      (node (ref "LED46") (pin "A") (pinfunction "A_A") (pintype "passive"))
      (node (ref "R62") (pin "P$1") (pinfunction "1_P$1") (pintype "passive"))
    )
    (net (code "121") (name "Net-(R63-1)") (class "Default")
      (node (ref "LED63") (pin "A") (pinfunction "A_A") (pintype "passive"))
      (node (ref "R63") (pin "P$1") (pinfunction "1_P$1") (pintype "passive"))
    )
    (net (code "122") (name "Net-(R64-1)") (class "Default")
      (node (ref "LED64") (pin "A") (pinfunction "A_A") (pintype "passive"))
      (node (ref "R64") (pin "P$1") (pinfunction "1_P$1") (pintype "passive"))
    )
    (net (code "123") (name "Net-(R65-1)") (class "Default")
      (node (ref "LED65") (pin "A") (pinfunction "A_A") (pintype "passive"))
      (node (ref "R65") (pin "P$1") (pinfunction "1_P$1") (pintype "passive"))
    )
    (net (code "124") (name "Net-(R66-1)") (class "Default")
      (node (ref "LED50") (pin "A") (pinfunction "A_A") (pintype "passive"))
      (node (ref "R66") (pin "P$1") (pinfunction "1_P$1") (pintype "passive"))
    )
    (net (code "125") (name "Net-(R67-1)") (class "Default")
      (node (ref "LED67") (pin "A") (pinfunction "A_A") (pintype "passive"))
      (node (ref "R67") (pin "P$1") (pinfunction "1_P$1") (pintype "passive"))
    )
    (net (code "126") (name "Net-(R68-1)") (class "Default")
      (node (ref "LED54") (pin "A") (pinfunction "A_A") (pintype "passive"))
      (node (ref "R68") (pin "P$1") (pinfunction "1_P$1") (pintype "passive"))
    )
    (net (code "127") (name "Net-(R69-1)") (class "Default")
      (node (ref "LED69") (pin "A") (pinfunction "A_A") (pintype "passive"))
      (node (ref "R69") (pin "P$1") (pinfunction "1_P$1") (pintype "passive"))
    )
    (net (code "128") (name "Net-(R70-1)") (class "Default")
      (node (ref "LED58") (pin "A") (pinfunction "A_A") (pintype "passive"))
      (node (ref "R70") (pin "P$1") (pinfunction "1_P$1") (pintype "passive"))
    )
    (net (code "129") (name "Net-(R71-1)") (class "Default")
      (node (ref "LED71") (pin "A") (pinfunction "A_A") (pintype "passive"))
      (node (ref "R71") (pin "P$1") (pinfunction "1_P$1") (pintype "passive"))
    )
    (net (code "130") (name "Net-(R73-1)") (class "Default")
      (node (ref "LED73") (pin "A") (pinfunction "A_A") (pintype "passive"))
      (node (ref "R73") (pin "P$1") (pinfunction "1_P$1") (pintype "passive"))
    )
    (net (code "131") (name "Net-(R75-1)") (class "Default")
      (node (ref "LED75") (pin "A") (pinfunction "A_A") (pintype "passive"))
      (node (ref "R75") (pin "P$1") (pinfunction "1_P$1") (pintype "passive"))
    )
    (net (code "132") (name "Net-(R76-1)") (class "Default")
      (node (ref "LED76") (pin "A") (pinfunction "A_A") (pintype "passive"))
      (node (ref "R76") (pin "P$1") (pinfunction "1_P$1") (pintype "passive"))
    )
    (net (code "133") (name "Net-(R77-1)") (class "Default")
      (node (ref "LED77") (pin "A") (pinfunction "A_A") (pintype "passive"))
      (node (ref "R77") (pin "P$1") (pinfunction "1_P$1") (pintype "passive"))
    )
    (net (code "134") (name "Net-(R79-1)") (class "Default")
      (node (ref "LED79") (pin "A") (pinfunction "A_A") (pintype "passive"))
      (node (ref "R79") (pin "P$1") (pinfunction "1_P$1") (pintype "passive"))
    )
    (net (code "135") (name "Net-(R80-1)") (class "Default")
      (node (ref "LED80") (pin "A") (pinfunction "A_A") (pintype "passive"))
      (node (ref "R80") (pin "P$1") (pinfunction "1_P$1") (pintype "passive"))
    )
    (net (code "136") (name "Net-(R81-1)") (class "Default")
      (node (ref "LED81") (pin "A") (pinfunction "A_A") (pintype "passive"))
      (node (ref "R81") (pin "P$1") (pinfunction "1_P$1") (pintype "passive"))
    )
    (net (code "137") (name "Net-(R83-1)") (class "Default")
      (node (ref "LED83") (pin "A") (pinfunction "A_A") (pintype "passive"))
      (node (ref "R83") (pin "P$1") (pinfunction "1_P$1") (pintype "passive"))
    )
    (net (code "138") (name "Net-(R84-1)") (class "Default")
      (node (ref "LED84") (pin "A") (pinfunction "A_A") (pintype "passive"))
      (node (ref "R84") (pin "P$1") (pinfunction "1_P$1") (pintype "passive"))
    )
    (net (code "139") (name "Net-(R85-1)") (class "Default")
      (node (ref "LED85") (pin "A") (pinfunction "A_A") (pintype "passive"))
      (node (ref "R85") (pin "P$1") (pinfunction "1_P$1") (pintype "passive"))
    )
    (net (code "140") (name "Net-(R87-1)") (class "Default")
      (node (ref "LED87") (pin "A") (pinfunction "A_A") (pintype "passive"))
      (node (ref "R87") (pin "P$1") (pinfunction "1_P$1") (pintype "passive"))
    )
    (net (code "141") (name "Net-(R89-1)") (class "Default")
      (node (ref "LED89") (pin "A") (pinfunction "A_A") (pintype "passive"))
      (node (ref "R89") (pin "P$1") (pinfunction "1_P$1") (pintype "passive"))
    )
    (net (code "142") (name "Net-(R91-1)") (class "Default")
      (node (ref "LED91") (pin "A") (pinfunction "A_A") (pintype "passive"))
      (node (ref "R91") (pin "P$1") (pinfunction "1_P$1") (pintype "passive"))
    )
    (net (code "143") (name "Net-(R93-1)") (class "Default")
      (node (ref "LED93") (pin "A") (pinfunction "A_A") (pintype "passive"))
      (node (ref "R93") (pin "P$1") (pinfunction "1_P$1") (pintype "passive"))
    )
    (net (code "144") (name "Net-(R95-1)") (class "Default")
      (node (ref "LED95") (pin "A") (pinfunction "A_A") (pintype "passive"))
      (node (ref "R95") (pin "P$1") (pinfunction "1_P$1") (pintype "passive"))
    )
    (net (code "145") (name "Net-(R97-1)") (class "Default")
      (node (ref "LED97") (pin "A") (pinfunction "A_A") (pintype "passive"))
      (node (ref "R97") (pin "P$1") (pinfunction "1_P$1") (pintype "passive"))
    )
    (net (code "146") (name "Net-(R99-1)") (class "Default")
      (node (ref "LED99") (pin "A") (pinfunction "A_A") (pintype "passive"))
      (node (ref "R99") (pin "P$1") (pinfunction "1_P$1") (pintype "passive"))
    )
    (net (code "147") (name "Net-(RYS1-2)") (class "Default")
      (node (ref "RYS1") (pin "P$2") (pinfunction "2_P$2") (pintype "passive"))
      (node (ref "U1") (pin "1") (pinfunction "B(2)_1") (pintype "input"))
    )
    (net (code "148") (name "Net-(RYS2-2)") (class "Default")
      (node (ref "RYS2") (pin "P$2") (pinfunction "2_P$2") (pintype "passive"))
      (node (ref "U2") (pin "1") (pinfunction "B(2)_1") (pintype "input"))
    )
    (net (code "149") (name "Net-(RYS3-2)") (class "Default")
      (node (ref "RYS3") (pin "P$2") (pinfunction "2_P$2") (pintype "passive"))
      (node (ref "U3") (pin "1") (pinfunction "B(2)_1") (pintype "input"))
    )
    (net (code "150") (name "Net-(RYS4-2)") (class "Default")
      (node (ref "RYS4") (pin "P$2") (pinfunction "2_P$2") (pintype "passive"))
      (node (ref "U4") (pin "1") (pinfunction "B(2)_1") (pintype "input"))
    )
    (net (code "151") (name "Net-(RYS5-2)") (class "Default")
      (node (ref "RYS5") (pin "P$2") (pinfunction "2_P$2") (pintype "passive"))
      (node (ref "U5") (pin "1") (pinfunction "B(2)_1") (pintype "input"))
    )
    (net (code "152") (name "Net-(RYS6-2)") (class "Default")
      (node (ref "RYS6") (pin "P$2") (pinfunction "2_P$2") (pintype "passive"))
      (node (ref "U6") (pin "1") (pinfunction "B(2)_1") (pintype "input"))
    )
    (net (code "153") (name "Net-(RYS7-2)") (class "Default")
      (node (ref "RYS7") (pin "P$2") (pinfunction "2_P$2") (pintype "passive"))
      (node (ref "U7") (pin "1") (pinfunction "B(2)_1") (pintype "input"))
    )
    (net (code "154") (name "Net-(RYS9-2)") (class "Default")
      (node (ref "RYS9") (pin "P$2") (pinfunction "2_P$2") (pintype "passive"))
      (node (ref "U8") (pin "1") (pinfunction "B(2)_1") (pintype "input"))
    )
    (net (code "155") (name "Net-(RYS10-2)") (class "Default")
      (node (ref "RYS10") (pin "P$2") (pinfunction "2_P$2") (pintype "passive"))
      (node (ref "U9") (pin "1") (pinfunction "B(2)_1") (pintype "input"))
    )
    (net (code "156") (name "Net-(RYS11-2)") (class "Default")
      (node (ref "RYS11") (pin "P$2") (pinfunction "2_P$2") (pintype "passive"))
      (node (ref "U10") (pin "1") (pinfunction "B(2)_1") (pintype "input"))
    )
    (net (code "157") (name "Net-(RYS12-2)") (class "Default")
      (node (ref "RYS12") (pin "P$2") (pinfunction "2_P$2") (pintype "passive"))
      (node (ref "U11") (pin "1") (pinfunction "B(2)_1") (pintype "input"))
    )
    (net (code "158") (name "Net-(RYS13-2)") (class "Default")
      (node (ref "RYS13") (pin "P$2") (pinfunction "2_P$2") (pintype "passive"))
      (node (ref "U12") (pin "1") (pinfunction "B(2)_1") (pintype "input"))
    )
    (net (code "159") (name "Net-(RYS14-2)") (class "Default")
      (node (ref "RYS14") (pin "P$2") (pinfunction "2_P$2") (pintype "passive"))
      (node (ref "U13") (pin "1") (pinfunction "B(2)_1") (pintype "input"))
    )
    (net (code "160") (name "Net-(RYS15-2)") (class "Default")
      (node (ref "RYS15") (pin "P$2") (pinfunction "2_P$2") (pintype "passive"))
      (node (ref "U14") (pin "1") (pinfunction "B(2)_1") (pintype "input"))
    )
    (net (code "161") (name "Net-(RYS16-2)") (class "Default")
      (node (ref "RYS16") (pin "P$2") (pinfunction "2_P$2") (pintype "passive"))
      (node (ref "U15") (pin "1") (pinfunction "B(2)_1") (pintype "input"))
    )
    (net (code "162") (name "Net-(RYS17-2)") (class "Default")
      (node (ref "RYS17") (pin "P$2") (pinfunction "2_P$2") (pintype "passive"))
      (node (ref "U16") (pin "1") (pinfunction "B(2)_1") (pintype "input"))
    )
    (net (code "163") (name "Net-(RYS18-2)") (class "Default")
      (node (ref "RYS18") (pin "P$2") (pinfunction "2_P$2") (pintype "passive"))
      (node (ref "U17") (pin "1") (pinfunction "B(2)_1") (pintype "input"))
    )
    (net (code "164") (name "Net-(RYS19-2)") (class "Default")
      (node (ref "RYS19") (pin "P$2") (pinfunction "2_P$2") (pintype "passive"))
      (node (ref "U18") (pin "1") (pinfunction "B(2)_1") (pintype "input"))
    )
    (net (code "165") (name "Net-(RYS20-2)") (class "Default")
      (node (ref "RYS20") (pin "P$2") (pinfunction "2_P$2") (pintype "passive"))
      (node (ref "U20") (pin "1") (pinfunction "B(2)_1") (pintype "input"))
    )
    (net (code "166") (name "Net-(RYS21-2)") (class "Default")
      (node (ref "RYS21") (pin "P$2") (pinfunction "2_P$2") (pintype "passive"))
      (node (ref "U21") (pin "1") (pinfunction "B(2)_1") (pintype "input"))
    )
    (net (code "167") (name "Net-(RYS22-2)") (class "Default")
      (node (ref "RYS22") (pin "P$2") (pinfunction "2_P$2") (pintype "passive"))
      (node (ref "U22") (pin "1") (pinfunction "B(2)_1") (pintype "input"))
    )
    (net (code "168") (name "Net-(RYS23-2)") (class "Default")
      (node (ref "RYS23") (pin "P$2") (pinfunction "2_P$2") (pintype "passive"))
      (node (ref "U23") (pin "1") (pinfunction "B(2)_1") (pintype "input"))
    )
    (net (code "169") (name "Net-(RYS24-2)") (class "Default")
      (node (ref "RYS24") (pin "P$2") (pinfunction "2_P$2") (pintype "passive"))
      (node (ref "U24") (pin "1") (pinfunction "B(2)_1") (pintype "input"))
    )
    (net (code "170") (name "Net-(RYS25-2)") (class "Default")
      (node (ref "RYS25") (pin "P$2") (pinfunction "2_P$2") (pintype "passive"))
      (node (ref "U25") (pin "1") (pinfunction "B(2)_1") (pintype "input"))
    )
    (net (code "171") (name "Net-(RYS26-2)") (class "Default")
      (node (ref "RYS26") (pin "P$2") (pinfunction "2_P$2") (pintype "passive"))
      (node (ref "U26") (pin "1") (pinfunction "B(2)_1") (pintype "input"))
    )
    (net (code "172") (name "Net-(RYS27-2)") (class "Default")
      (node (ref "RYS27") (pin "P$2") (pinfunction "2_P$2") (pintype "passive"))
      (node (ref "U27") (pin "1") (pinfunction "B(2)_1") (pintype "input"))
    )
    (net (code "173") (name "Net-(RYS28-2)") (class "Default")
      (node (ref "RYS28") (pin "P$2") (pinfunction "2_P$2") (pintype "passive"))
      (node (ref "U28") (pin "1") (pinfunction "B(2)_1") (pintype "input"))
    )
    (net (code "174") (name "Net-(RYS29-2)") (class "Default")
      (node (ref "RYS29") (pin "P$2") (pinfunction "2_P$2") (pintype "passive"))
      (node (ref "U29") (pin "1") (pinfunction "B(2)_1") (pintype "input"))
    )
    (net (code "175") (name "Net-(RYS30-2)") (class "Default")
      (node (ref "RYS30") (pin "P$2") (pinfunction "2_P$2") (pintype "passive"))
      (node (ref "U30") (pin "1") (pinfunction "B(2)_1") (pintype "input"))
    )
    (net (code "176") (name "Net-(RYS31-2)") (class "Default")
      (node (ref "RYS31") (pin "P$2") (pinfunction "2_P$2") (pintype "passive"))
      (node (ref "U31") (pin "1") (pinfunction "B(2)_1") (pintype "input"))
    )
    (net (code "177") (name "Net-(RYS32-2)") (class "Default")
      (node (ref "RYS32") (pin "P$2") (pinfunction "2_P$2") (pintype "passive"))
      (node (ref "U32") (pin "1") (pinfunction "B(2)_1") (pintype "input"))
    )
    (net (code "178") (name "Net-(RYS33-2)") (class "Default")
      (node (ref "RYS33") (pin "P$2") (pinfunction "2_P$2") (pintype "passive"))
      (node (ref "U33") (pin "1") (pinfunction "B(2)_1") (pintype "input"))
    )
    (net (code "179") (name "Net-(RYS34-2)") (class "Default")
      (node (ref "RYS34") (pin "P$2") (pinfunction "2_P$2") (pintype "passive"))
      (node (ref "U34") (pin "1") (pinfunction "B(2)_1") (pintype "input"))
    )
    (net (code "180") (name "Net-(RYS35-2)") (class "Default")
      (node (ref "RYS35") (pin "P$2") (pinfunction "2_P$2") (pintype "passive"))
      (node (ref "U35") (pin "1") (pinfunction "B(2)_1") (pintype "input"))
    )
    (net (code "181") (name "Net-(RYS36-2)") (class "Default")
      (node (ref "RYS36") (pin "P$2") (pinfunction "2_P$2") (pintype "passive"))
      (node (ref "U36") (pin "1") (pinfunction "B(2)_1") (pintype "input"))
    )
    (net (code "182") (name "Net-(RYS37-2)") (class "Default")
      (node (ref "RYS37") (pin "P$2") (pinfunction "2_P$2") (pintype "passive"))
      (node (ref "U37") (pin "1") (pinfunction "B(2)_1") (pintype "input"))
    )
    (net (code "183") (name "Net-(RYS38-2)") (class "Default")
      (node (ref "RYS38") (pin "P$2") (pinfunction "2_P$2") (pintype "passive"))
      (node (ref "U38") (pin "1") (pinfunction "B(2)_1") (pintype "input"))
    )
    (net (code "184") (name "Net-(RYS39-2)") (class "Default")
      (node (ref "RYS39") (pin "P$2") (pinfunction "2_P$2") (pintype "passive"))
      (node (ref "U39") (pin "1") (pinfunction "B(2)_1") (pintype "input"))
    )
    (net (code "185") (name "Net-(RYS40-2)") (class "Default")
      (node (ref "RYS40") (pin "P$2") (pinfunction "2_P$2") (pintype "passive"))
      (node (ref "U40") (pin "1") (pinfunction "B(2)_1") (pintype "input"))
    )
    (net (code "186") (name "Net-(RYS42-2)") (class "Default")
      (node (ref "RYS42") (pin "P$2") (pinfunction "2_P$2") (pintype "passive"))
      (node (ref "U42") (pin "1") (pinfunction "B(2)_1") (pintype "input"))
    )
    (net (code "187") (name "Net-(RYS43-2)") (class "Default")
      (node (ref "RYS43") (pin "P$2") (pinfunction "2_P$2") (pintype "passive"))
      (node (ref "U43") (pin "1") (pinfunction "B(2)_1") (pintype "input"))
    )
    (net (code "188") (name "Net-(RYS44-2)") (class "Default")
      (node (ref "RYS44") (pin "P$2") (pinfunction "2_P$2") (pintype "passive"))
      (node (ref "U44") (pin "1") (pinfunction "B(2)_1") (pintype "input"))
    )
    (net (code "189") (name "Net-(RYS46-2)") (class "Default")
      (node (ref "RYS46") (pin "P$2") (pinfunction "2_P$2") (pintype "passive"))
      (node (ref "U46") (pin "1") (pinfunction "B(2)_1") (pintype "input"))
    )
    (net (code "190") (name "Net-(RYS48-2)") (class "Default")
      (node (ref "RYS48") (pin "P$2") (pinfunction "2_P$2") (pintype "passive"))
      (node (ref "U48") (pin "1") (pinfunction "B(2)_1") (pintype "input"))
    )
    (net (code "191") (name "Net-(RYS50-2)") (class "Default")
      (node (ref "RYS50") (pin "P$2") (pinfunction "2_P$2") (pintype "passive"))
      (node (ref "U50") (pin "1") (pinfunction "B(2)_1") (pintype "input"))
    )
    (net (code "192") (name "Net-(RYS52-2)") (class "Default")
      (node (ref "RYS52") (pin "P$2") (pinfunction "2_P$2") (pintype "passive"))
      (node (ref "U52") (pin "1") (pinfunction "B(2)_1") (pintype "input"))
    )
    (net (code "193") (name "Net-(RYS54-2)") (class "Default")
      (node (ref "RYS54") (pin "P$2") (pinfunction "2_P$2") (pintype "passive"))
      (node (ref "U54") (pin "1") (pinfunction "B(2)_1") (pintype "input"))
    )
    (net (code "194") (name "Net-(RYS55-2)") (class "Default")
      (node (ref "RYS55") (pin "P$2") (pinfunction "2_P$2") (pintype "passive"))
      (node (ref "U55") (pin "1") (pinfunction "B(2)_1") (pintype "input"))
    )
    (net (code "195") (name "Net-(RYS56-2)") (class "Default")
      (node (ref "RYS56") (pin "P$2") (pinfunction "2_P$2") (pintype "passive"))
      (node (ref "U56") (pin "1") (pinfunction "B(2)_1") (pintype "input"))
    )
    (net (code "196") (name "Net-(RYS58-2)") (class "Default")
      (node (ref "RYS58") (pin "P$2") (pinfunction "2_P$2") (pintype "passive"))
      (node (ref "U58") (pin "1") (pinfunction "B(2)_1") (pintype "input"))
    )
    (net (code "197") (name "Net-(RYS59-2)") (class "Default")
      (node (ref "RYS59") (pin "P$2") (pinfunction "2_P$2") (pintype "passive"))
      (node (ref "U59") (pin "1") (pinfunction "B(2)_1") (pintype "input"))
    )
    (net (code "198") (name "Net-(RYS60-2)") (class "Default")
      (node (ref "RYS60") (pin "P$2") (pinfunction "2_P$2") (pintype "passive"))
      (node (ref "U60") (pin "1") (pinfunction "B(2)_1") (pintype "input"))
    )
    (net (code "199") (name "Net-(RYS62-2)") (class "Default")
      (node (ref "RYS62") (pin "P$2") (pinfunction "2_P$2") (pintype "passive"))
      (node (ref "U62") (pin "1") (pinfunction "B(2)_1") (pintype "input"))
    )
    (net (code "200") (name "Net-(RYS63-2)") (class "Default")
      (node (ref "RYS63") (pin "P$2") (pinfunction "2_P$2") (pintype "passive"))
      (node (ref "U63") (pin "1") (pinfunction "B(2)_1") (pintype "input"))
    )
    (net (code "201") (name "Net-(RYS64-2)") (class "Default")
      (node (ref "RYS64") (pin "P$2") (pinfunction "2_P$2") (pintype "passive"))
      (node (ref "U64") (pin "1") (pinfunction "B(2)_1") (pintype "input"))
    )
    (net (code "202") (name "Net-(RYS66-2)") (class "Default")
      (node (ref "RYS66") (pin "P$2") (pinfunction "2_P$2") (pintype "passive"))
      (node (ref "U66") (pin "1") (pinfunction "B(2)_1") (pintype "input"))
    )
    (net (code "203") (name "Net-(RYS68-2)") (class "Default")
      (node (ref "RYS68") (pin "P$2") (pinfunction "2_P$2") (pintype "passive"))
      (node (ref "U68") (pin "1") (pinfunction "B(2)_1") (pintype "input"))
    )
    (net (code "204") (name "Net-(RYS70-2)") (class "Default")
      (node (ref "RYS70") (pin "P$2") (pinfunction "2_P$2") (pintype "passive"))
      (node (ref "U70") (pin "1") (pinfunction "B(2)_1") (pintype "input"))
    )
    (net (code "205") (name "Net-(RYS72-2)") (class "Default")
      (node (ref "RYS72") (pin "P$2") (pinfunction "2_P$2") (pintype "passive"))
      (node (ref "U72") (pin "1") (pinfunction "B(2)_1") (pintype "input"))
    )
    (net (code "206") (name "Net-(RYS74-2)") (class "Default")
      (node (ref "RYS74") (pin "P$2") (pinfunction "2_P$2") (pintype "passive"))
      (node (ref "U74") (pin "1") (pinfunction "B(2)_1") (pintype "input"))
    )
    (net (code "207") (name "Net-(RYS76-2)") (class "Default")
      (node (ref "RYS76") (pin "P$2") (pinfunction "2_P$2") (pintype "passive"))
      (node (ref "U76") (pin "1") (pinfunction "B(2)_1") (pintype "input"))
    )
    (net (code "208") (name "Net-(RYS78-2)") (class "Default")
      (node (ref "RYS78") (pin "P$2") (pinfunction "2_P$2") (pintype "passive"))
      (node (ref "U78") (pin "1") (pinfunction "B(2)_1") (pintype "input"))
    )
    (net (code "209") (name "Net-(U1-C(3))") (class "Default")
      (node (ref "LED23") (pin "C") (pinfunction "C_C") (pintype "passive"))
      (node (ref "U1") (pin "3") (pinfunction "C(3)_3") (pintype "input"))
    )
    (net (code "210") (name "Net-(U2-C(3))") (class "Default")
      (node (ref "LED24") (pin "C") (pinfunction "C_C") (pintype "passive"))
      (node (ref "U2") (pin "3") (pinfunction "C(3)_3") (pintype "input"))
    )
    (net (code "211") (name "Net-(U3-C(3))") (class "Default")
      (node (ref "LED25") (pin "C") (pinfunction "C_C") (pintype "passive"))
      (node (ref "U3") (pin "3") (pinfunction "C(3)_3") (pintype "input"))
    )
    (net (code "212") (name "Net-(U4-C(3))") (class "Default")
      (node (ref "LED26") (pin "C") (pinfunction "C_C") (pintype "passive"))
      (node (ref "U4") (pin "3") (pinfunction "C(3)_3") (pintype "input"))
    )
    (net (code "213") (name "Net-(U5-C(3))") (class "Default")
      (node (ref "LED27") (pin "C") (pinfunction "C_C") (pintype "passive"))
      (node (ref "U5") (pin "3") (pinfunction "C(3)_3") (pintype "input"))
    )
    (net (code "214") (name "Net-(U6-C(3))") (class "Default")
      (node (ref "LED28") (pin "C") (pinfunction "C_C") (pintype "passive"))
      (node (ref "U6") (pin "3") (pinfunction "C(3)_3") (pintype "input"))
    )
    (net (code "215") (name "Net-(U7-C(3))") (class "Default")
      (node (ref "LED29") (pin "C") (pinfunction "C_C") (pintype "passive"))
      (node (ref "U7") (pin "3") (pinfunction "C(3)_3") (pintype "input"))
    )
    (net (code "216") (name "Net-(U8-C(3))") (class "Default")
      (node (ref "LED30") (pin "C") (pinfunction "C_C") (pintype "passive"))
      (node (ref "U8") (pin "3") (pinfunction "C(3)_3") (pintype "input"))
    )
    (net (code "217") (name "Net-(U9-C(3))") (class "Default")
      (node (ref "LED31") (pin "C") (pinfunction "C_C") (pintype "passive"))
      (node (ref "U9") (pin "3") (pinfunction "C(3)_3") (pintype "input"))
    )
    (net (code "218") (name "Net-(U10-C(3))") (class "Default")
      (node (ref "LED32") (pin "C") (pinfunction "C_C") (pintype "passive"))
      (node (ref "U10") (pin "3") (pinfunction "C(3)_3") (pintype "input"))
    )
    (net (code "219") (name "Net-(U11-C(3))") (class "Default")
      (node (ref "LED33") (pin "C") (pinfunction "C_C") (pintype "passive"))
      (node (ref "U11") (pin "3") (pinfunction "C(3)_3") (pintype "input"))
    )
    (net (code "220") (name "Net-(U12-C(3))") (class "Default")
      (node (ref "LED34") (pin "C") (pinfunction "C_C") (pintype "passive"))
      (node (ref "U12") (pin "3") (pinfunction "C(3)_3") (pintype "input"))
    )
    (net (code "221") (name "Net-(U13-C(3))") (class "Default")
      (node (ref "LED35") (pin "C") (pinfunction "C_C") (pintype "passive"))
      (node (ref "U13") (pin "3") (pinfunction "C(3)_3") (pintype "input"))
    )
    (net (code "222") (name "Net-(U14-C(3))") (class "Default")
      (node (ref "LED36") (pin "C") (pinfunction "C_C") (pintype "passive"))
      (node (ref "U14") (pin "3") (pinfunction "C(3)_3") (pintype "input"))
    )
    (net (code "223") (name "Net-(U15-C(3))") (class "Default")
      (node (ref "LED37") (pin "C") (pinfunction "C_C") (pintype "passive"))
      (node (ref "U15") (pin "3") (pinfunction "C(3)_3") (pintype "input"))
    )
    (net (code "224") (name "Net-(U16-C(3))") (class "Default")
      (node (ref "LED38") (pin "C") (pinfunction "C_C") (pintype "passive"))
      (node (ref "U16") (pin "3") (pinfunction "C(3)_3") (pintype "input"))
    )
    (net (code "225") (name "Net-(U17-C(3))") (class "Default")
      (node (ref "LED39") (pin "C") (pinfunction "C_C") (pintype "passive"))
      (node (ref "U17") (pin "3") (pinfunction "C(3)_3") (pintype "input"))
    )
    (net (code "226") (name "Net-(U18-C(3))") (class "Default")
      (node (ref "LED40") (pin "C") (pinfunction "C_C") (pintype "passive"))
      (node (ref "U18") (pin "3") (pinfunction "C(3)_3") (pintype "input"))
    )
    (net (code "227") (name "Net-(U20-C(3))") (class "Default")
      (node (ref "LED41") (pin "C") (pinfunction "C_C") (pintype "passive"))
      (node (ref "U20") (pin "3") (pinfunction "C(3)_3") (pintype "input"))
    )
    (net (code "228") (name "Net-(U21-C(3))") (class "Default")
      (node (ref "LED42") (pin "C") (pinfunction "C_C") (pintype "passive"))
      (node (ref "U21") (pin "3") (pinfunction "C(3)_3") (pintype "input"))
    )
    (net (code "229") (name "Net-(U22-C(3))") (class "Default")
      (node (ref "LED43") (pin "C") (pinfunction "C_C") (pintype "passive"))
      (node (ref "U22") (pin "3") (pinfunction "C(3)_3") (pintype "input"))
    )
    (net (code "230") (name "Net-(U23-C(3))") (class "Default")
      (node (ref "LED44") (pin "C") (pinfunction "C_C") (pintype "passive"))
      (node (ref "U23") (pin "3") (pinfunction "C(3)_3") (pintype "input"))
    )
    (net (code "231") (name "Net-(U24-C(3))") (class "Default")
      (node (ref "LED45") (pin "C") (pinfunction "C_C") (pintype "passive"))
      (node (ref "U24") (pin "3") (pinfunction "C(3)_3") (pintype "input"))
    )
    (net (code "232") (name "Net-(U25-C(3))") (class "Default")
      (node (ref "LED46") (pin "C") (pinfunction "C_C") (pintype "passive"))
      (node (ref "U25") (pin "3") (pinfunction "C(3)_3") (pintype "input"))
    )
    (net (code "233") (name "Net-(U26-C(3))") (class "Default")
      (node (ref "LED47") (pin "C") (pinfunction "C_C") (pintype "passive"))
      (node (ref "U26") (pin "3") (pinfunction "C(3)_3") (pintype "input"))
    )
    (net (code "234") (name "Net-(U27-C(3))") (class "Default")
      (node (ref "LED48") (pin "C") (pinfunction "C_C") (pintype "passive"))
      (node (ref "U27") (pin "3") (pinfunction "C(3)_3") (pintype "input"))
    )
    (net (code "235") (name "Net-(U28-C(3))") (class "Default")
      (node (ref "LED49") (pin "C") (pinfunction "C_C") (pintype "passive"))
      (node (ref "U28") (pin "3") (pinfunction "C(3)_3") (pintype "input"))
    )
    (net (code "236") (name "Net-(U29-C(3))") (class "Default")
      (node (ref "LED50") (pin "C") (pinfunction "C_C") (pintype "passive"))
      (node (ref "U29") (pin "3") (pinfunction "C(3)_3") (pintype "input"))
    )
    (net (code "237") (name "Net-(U30-C(3))") (class "Default")
      (node (ref "LED51") (pin "C") (pinfunction "C_C") (pintype "passive"))
      (node (ref "U30") (pin "3") (pinfunction "C(3)_3") (pintype "input"))
    )
    (net (code "238") (name "Net-(U31-C(3))") (class "Default")
      (node (ref "LED52") (pin "C") (pinfunction "C_C") (pintype "passive"))
      (node (ref "U31") (pin "3") (pinfunction "C(3)_3") (pintype "input"))
    )
    (net (code "239") (name "Net-(U32-C(3))") (class "Default")
      (node (ref "LED53") (pin "C") (pinfunction "C_C") (pintype "passive"))
      (node (ref "U32") (pin "3") (pinfunction "C(3)_3") (pintype "input"))
    )
    (net (code "240") (name "Net-(U33-C(3))") (class "Default")
      (node (ref "LED54") (pin "C") (pinfunction "C_C") (pintype "passive"))
      (node (ref "U33") (pin "3") (pinfunction "C(3)_3") (pintype "input"))
    )
    (net (code "241") (name "Net-(U34-C(3))") (class "Default")
      (node (ref "LED55") (pin "C") (pinfunction "C_C") (pintype "passive"))
      (node (ref "U34") (pin "3") (pinfunction "C(3)_3") (pintype "input"))
    )
    (net (code "242") (name "Net-(U35-C(3))") (class "Default")
      (node (ref "LED56") (pin "C") (pinfunction "C_C") (pintype "passive"))
      (node (ref "U35") (pin "3") (pinfunction "C(3)_3") (pintype "input"))
    )
    (net (code "243") (name "Net-(U36-C(3))") (class "Default")
      (node (ref "LED57") (pin "C") (pinfunction "C_C") (pintype "passive"))
      (node (ref "U36") (pin "3") (pinfunction "C(3)_3") (pintype "input"))
    )
    (net (code "244") (name "Net-(U37-C(3))") (class "Default")
      (node (ref "LED58") (pin "C") (pinfunction "C_C") (pintype "passive"))
      (node (ref "U37") (pin "3") (pinfunction "C(3)_3") (pintype "input"))
    )
    (net (code "245") (name "Net-(U38-C(3))") (class "Default")
      (node (ref "LED59") (pin "C") (pinfunction "C_C") (pintype "passive"))
      (node (ref "U38") (pin "3") (pinfunction "C(3)_3") (pintype "input"))
    )
    (net (code "246") (name "Net-(U39-C(3))") (class "Default")
      (node (ref "LED60") (pin "C") (pinfunction "C_C") (pintype "passive"))
      (node (ref "U39") (pin "3") (pinfunction "C(3)_3") (pintype "input"))
    )
    (net (code "247") (name "Net-(U40-C(3))") (class "Default")
      (node (ref "LED61") (pin "C") (pinfunction "C_C") (pintype "passive"))
      (node (ref "U40") (pin "3") (pinfunction "C(3)_3") (pintype "input"))
    )
    (net (code "248") (name "Net-(U42-C(3))") (class "Default")
      (node (ref "LED63") (pin "C") (pinfunction "C_C") (pintype "passive"))
      (node (ref "U42") (pin "3") (pinfunction "C(3)_3") (pintype "input"))
    )
    (net (code "249") (name "Net-(U43-C(3))") (class "Default")
      (node (ref "LED64") (pin "C") (pinfunction "C_C") (pintype "passive"))
      (node (ref "U43") (pin "3") (pinfunction "C(3)_3") (pintype "input"))
    )
    (net (code "250") (name "Net-(U44-C(3))") (class "Default")
      (node (ref "LED65") (pin "C") (pinfunction "C_C") (pintype "passive"))
      (node (ref "U44") (pin "3") (pinfunction "C(3)_3") (pintype "input"))
    )
    (net (code "251") (name "Net-(U46-C(3))") (class "Default")
      (node (ref "LED67") (pin "C") (pinfunction "C_C") (pintype "passive"))
      (node (ref "U46") (pin "3") (pinfunction "C(3)_3") (pintype "input"))
    )
    (net (code "252") (name "Net-(U48-C(3))") (class "Default")
      (node (ref "LED69") (pin "C") (pinfunction "C_C") (pintype "passive"))
      (node (ref "U48") (pin "3") (pinfunction "C(3)_3") (pintype "input"))
    )
    (net (code "253") (name "Net-(U50-C(3))") (class "Default")
      (node (ref "LED71") (pin "C") (pinfunction "C_C") (pintype "passive"))
      (node (ref "U50") (pin "3") (pinfunction "C(3)_3") (pintype "input"))
    )
    (net (code "254") (name "Net-(U52-C(3))") (class "Default")
      (node (ref "LED73") (pin "C") (pinfunction "C_C") (pintype "passive"))
      (node (ref "U52") (pin "3") (pinfunction "C(3)_3") (pintype "input"))
    )
    (net (code "255") (name "Net-(U54-C(3))") (class "Default")
      (node (ref "LED75") (pin "C") (pinfunction "C_C") (pintype "passive"))
      (node (ref "U54") (pin "3") (pinfunction "C(3)_3") (pintype "input"))
    )
    (net (code "256") (name "Net-(U55-C(3))") (class "Default")
      (node (ref "LED76") (pin "C") (pinfunction "C_C") (pintype "passive"))
      (node (ref "U55") (pin "3") (pinfunction "C(3)_3") (pintype "input"))
    )
    (net (code "257") (name "Net-(U56-C(3))") (class "Default")
      (node (ref "LED77") (pin "C") (pinfunction "C_C") (pintype "passive"))
      (node (ref "U56") (pin "3") (pinfunction "C(3)_3") (pintype "input"))
    )
    (net (code "258") (name "Net-(U58-C(3))") (class "Default")
      (node (ref "LED79") (pin "C") (pinfunction "C_C") (pintype "passive"))
      (node (ref "U58") (pin "3") (pinfunction "C(3)_3") (pintype "input"))
    )
    (net (code "259") (name "Net-(U59-C(3))") (class "Default")
      (node (ref "LED80") (pin "C") (pinfunction "C_C") (pintype "passive"))
      (node (ref "U59") (pin "3") (pinfunction "C(3)_3") (pintype "input"))
    )
    (net (code "260") (name "Net-(U60-C(3))") (class "Default")
      (node (ref "LED81") (pin "C") (pinfunction "C_C") (pintype "passive"))
      (node (ref "U60") (pin "3") (pinfunction "C(3)_3") (pintype "input"))
    )
    (net (code "261") (name "Net-(U62-C(3))") (class "Default")
      (node (ref "LED83") (pin "C") (pinfunction "C_C") (pintype "passive"))
      (node (ref "U62") (pin "3") (pinfunction "C(3)_3") (pintype "input"))
    )
    (net (code "262") (name "Net-(U63-C(3))") (class "Default")
      (node (ref "LED84") (pin "C") (pinfunction "C_C") (pintype "passive"))
      (node (ref "U63") (pin "3") (pinfunction "C(3)_3") (pintype "input"))
    )
    (net (code "263") (name "Net-(U64-C(3))") (class "Default")
      (node (ref "LED85") (pin "C") (pinfunction "C_C") (pintype "passive"))
      (node (ref "U64") (pin "3") (pinfunction "C(3)_3") (pintype "input"))
    )
    (net (code "264") (name "Net-(U66-C(3))") (class "Default")
      (node (ref "LED87") (pin "C") (pinfunction "C_C") (pintype "passive"))
      (node (ref "U66") (pin "3") (pinfunction "C(3)_3") (pintype "input"))
    )
    (net (code "265") (name "Net-(U68-C(3))") (class "Default")
      (node (ref "LED89") (pin "C") (pinfunction "C_C") (pintype "passive"))
      (node (ref "U68") (pin "3") (pinfunction "C(3)_3") (pintype "input"))
    )
    (net (code "266") (name "Net-(U70-C(3))") (class "Default")
      (node (ref "LED91") (pin "C") (pinfunction "C_C") (pintype "passive"))
      (node (ref "U70") (pin "3") (pinfunction "C(3)_3") (pintype "input"))
    )
    (net (code "267") (name "Net-(U72-C(3))") (class "Default")
      (node (ref "LED93") (pin "C") (pinfunction "C_C") (pintype "passive"))
      (node (ref "U72") (pin "3") (pinfunction "C(3)_3") (pintype "input"))
    )
    (net (code "268") (name "Net-(U74-C(3))") (class "Default")
      (node (ref "LED95") (pin "C") (pinfunction "C_C") (pintype "passive"))
      (node (ref "U74") (pin "3") (pinfunction "C(3)_3") (pintype "input"))
    )
    (net (code "269") (name "Net-(U76-C(3))") (class "Default")
      (node (ref "LED97") (pin "C") (pinfunction "C_C") (pintype "passive"))
      (node (ref "U76") (pin "3") (pinfunction "C(3)_3") (pintype "input"))
    )
    (net (code "270") (name "Net-(U78-C(3))") (class "Default")
      (node (ref "LED99") (pin "C") (pinfunction "C_C") (pintype "passive"))
      (node (ref "U78") (pin "3") (pinfunction "C(3)_3") (pintype "input"))
    )
    (net (code "271") (name "P1_02") (class "Default")
      (node (ref "J10") (pin "P$7") (pinfunction "P$7_P$7") (pintype "bidirectional"))
      (node (ref "RYS46") (pin "P$1") (pinfunction "1_P$1") (pintype "passive"))
    )
    (net (code "272") (name "P1_03") (class "Default")
      (node (ref "J10") (pin "P$8") (pinfunction "P$8_P$8") (pintype "bidirectional"))
      (node (ref "RYS5") (pin "P$1") (pinfunction "1_P$1") (pintype "passive"))
    )
    (net (code "273") (name "P1_06") (class "Default")
      (node (ref "J10") (pin "P$11") (pinfunction "P$11_P$11") (pintype "bidirectional"))
      (node (ref "RYS50") (pin "P$1") (pinfunction "1_P$1") (pintype "passive"))
    )
    (net (code "274") (name "P1_07") (class "Default")
      (node (ref "J10") (pin "P$12") (pinfunction "P$12_P$12") (pintype "bidirectional"))
      (node (ref "RYS10") (pin "P$1") (pinfunction "1_P$1") (pintype "passive"))
    )
    (net (code "275") (name "P1_11") (class "Default")
      (node (ref "J10") (pin "P$38") (pinfunction "P$38_P$38") (pintype "bidirectional"))
      (node (ref "RYS36") (pin "P$1") (pinfunction "1_P$1") (pintype "passive"))
    )
    (net (code "276") (name "P1_12") (class "Default")
      (node (ref "J10") (pin "P$37") (pinfunction "P$37_P$37") (pintype "bidirectional"))
      (node (ref "RYS76") (pin "P$1") (pinfunction "1_P$1") (pintype "passive"))
    )
    (net (code "277") (name "P1_13") (class "Default")
      (node (ref "J10") (pin "P$36") (pinfunction "P$36_P$36") (pintype "bidirectional"))
      (node (ref "RYS34") (pin "P$1") (pinfunction "1_P$1") (pintype "passive"))
    )
    (net (code "278") (name "P1_14") (class "Default")
      (node (ref "J10") (pin "P$35") (pinfunction "P$35_P$35") (pintype "bidirectional"))
      (node (ref "RYS74") (pin "P$1") (pinfunction "1_P$1") (pintype "passive"))
    )
    (net (code "279") (name "P1_15") (class "Default")
      (node (ref "J10") (pin "P$34") (pinfunction "P$34_P$34") (pintype "bidirectional"))
      (node (ref "RYS32") (pin "P$1") (pinfunction "1_P$1") (pintype "passive"))
    )
    (net (code "280") (name "P6_00") (class "Default")
      (node (ref "J10") (pin "P$13") (pinfunction "P$13_P$13") (pintype "bidirectional"))
      (node (ref "RYS52") (pin "P$1") (pinfunction "1_P$1") (pintype "passive"))
    )
    (net (code "281") (name "P6_01") (class "Default")
      (node (ref "J10") (pin "P$14") (pinfunction "P$14_P$14") (pintype "bidirectional"))
      (node (ref "RYS12") (pin "P$1") (pinfunction "1_P$1") (pintype "passive"))
    )
    (net (code "282") (name "P6_02") (class "Default")
      (node (ref "J10") (pin "P$15") (pinfunction "P$15_P$15") (pintype "bidirectional"))
      (node (ref "RYS54") (pin "P$1") (pinfunction "1_P$1") (pintype "passive"))
    )
    (net (code "283") (name "P6_03") (class "Default")
      (node (ref "J10") (pin "P$16") (pinfunction "P$16_P$16") (pintype "bidirectional"))
      (node (ref "RYS14") (pin "P$1") (pinfunction "1_P$1") (pintype "passive"))
    )
    (net (code "284") (name "P6_04") (class "Default")
      (node (ref "J10") (pin "P$17") (pinfunction "P$17_P$17") (pintype "bidirectional"))
      (node (ref "RYS56") (pin "P$1") (pinfunction "1_P$1") (pintype "passive"))
    )
    (net (code "285") (name "P6_05") (class "Default")
      (node (ref "J10") (pin "P$18") (pinfunction "P$18_P$18") (pintype "bidirectional"))
      (node (ref "RYS16") (pin "P$1") (pinfunction "1_P$1") (pintype "passive"))
    )
    (net (code "286") (name "P6_06") (class "Default")
      (node (ref "J10") (pin "P$19") (pinfunction "P$19_P$19") (pintype "bidirectional"))
      (node (ref "RYS58") (pin "P$1") (pinfunction "1_P$1") (pintype "passive"))
    )
    (net (code "287") (name "P6_07") (class "Default")
      (node (ref "J10") (pin "P$20") (pinfunction "P$20_P$20") (pintype "bidirectional"))
      (node (ref "RYS18") (pin "P$1") (pinfunction "1_P$1") (pintype "passive"))
    )
    (net (code "288") (name "P6_08") (class "Default")
      (node (ref "J10") (pin "P$33") (pinfunction "P$33_P$33") (pintype "bidirectional"))
      (node (ref "RYS72") (pin "P$1") (pinfunction "1_P$1") (pintype "passive"))
    )
    (net (code "289") (name "P6_09") (class "Default")
      (node (ref "J10") (pin "P$32") (pinfunction "P$32_P$32") (pintype "bidirectional"))
      (node (ref "RYS30") (pin "P$1") (pinfunction "1_P$1") (pintype "passive"))
    )
    (net (code "290") (name "P6_10") (class "Default")
      (node (ref "J10") (pin "P$31") (pinfunction "P$31_P$31") (pintype "bidirectional"))
      (node (ref "RYS70") (pin "P$1") (pinfunction "1_P$1") (pintype "passive"))
    )
    (net (code "291") (name "P6_11") (class "Default")
      (node (ref "J10") (pin "P$30") (pinfunction "P$30_P$30") (pintype "bidirectional"))
      (node (ref "RYS28") (pin "P$1") (pinfunction "1_P$1") (pintype "passive"))
    )
    (net (code "292") (name "P6_12") (class "Default")
      (node (ref "J10") (pin "P$29") (pinfunction "P$29_P$29") (pintype "bidirectional"))
      (node (ref "RYS68") (pin "P$1") (pinfunction "1_P$1") (pintype "passive"))
    )
    (net (code "293") (name "P6_13") (class "Default")
      (node (ref "J10") (pin "P$28") (pinfunction "P$28_P$28") (pintype "bidirectional"))
      (node (ref "RYS26") (pin "P$1") (pinfunction "1_P$1") (pintype "passive"))
    )
    (net (code "294") (name "P6_14") (class "Default")
      (node (ref "J10") (pin "P$27") (pinfunction "P$27_P$27") (pintype "bidirectional"))
      (node (ref "RYS66") (pin "P$1") (pinfunction "1_P$1") (pintype "passive"))
    )
    (net (code "295") (name "P6_15") (class "Default")
      (node (ref "J10") (pin "P$26") (pinfunction "P$26_P$26") (pintype "bidirectional"))
      (node (ref "RYS24") (pin "P$1") (pinfunction "1_P$1") (pintype "passive"))
    )
    (net (code "296") (name "P8_00") (class "Default")
      (node (ref "J10") (pin "P$4") (pinfunction "P$4_P$4") (pintype "bidirectional"))
      (node (ref "RYS2") (pin "P$1") (pinfunction "1_P$1") (pintype "passive"))
    )
    (net (code "297") (name "P8_01") (class "Default")
      (node (ref "J10") (pin "P$3") (pinfunction "P$3_P$3") (pintype "bidirectional"))
      (node (ref "RYS42") (pin "P$1") (pinfunction "1_P$1") (pintype "passive"))
    )
    (net (code "298") (name "P8_02") (class "Default")
      (node (ref "J10") (pin "P$2") (pinfunction "P$2_P$2") (pintype "bidirectional"))
      (node (ref "RYS1") (pin "P$1") (pinfunction "1_P$1") (pintype "passive"))
    )
    (net (code "299") (name "PA_00") (class "Default")
      (node (ref "J10") (pin "P$21") (pinfunction "P$21_P$21") (pintype "bidirectional"))
      (node (ref "RYS60") (pin "P$1") (pinfunction "1_P$1") (pintype "passive"))
    )
    (net (code "300") (name "PA_01") (class "Default")
      (node (ref "J10") (pin "P$22") (pinfunction "P$22_P$22") (pintype "bidirectional"))
      (node (ref "RYS20") (pin "P$1") (pinfunction "1_P$1") (pintype "passive"))
    )
    (net (code "301") (name "PA_08") (class "Default")
      (node (ref "J10") (pin "P$25") (pinfunction "P$25_P$25") (pintype "bidirectional"))
      (node (ref "RYS64") (pin "P$1") (pinfunction "1_P$1") (pintype "passive"))
    )
    (net (code "302") (name "PA_09") (class "Default")
      (node (ref "J10") (pin "P$24") (pinfunction "P$24_P$24") (pintype "bidirectional"))
      (node (ref "RYS22") (pin "P$1") (pinfunction "1_P$1") (pintype "passive"))
    )
    (net (code "303") (name "PA_10") (class "Default")
      (node (ref "J10") (pin "P$23") (pinfunction "P$23_P$23") (pintype "bidirectional"))
      (node (ref "RYS62") (pin "P$1") (pinfunction "1_P$1") (pintype "passive"))
    )
    (net (code "304") (name "VDD") (class "Default")
      (node (ref "J1") (pin "3") (pinfunction "3_3") (pintype "passive"))
      (node (ref "J1") (pin "4") (pinfunction "4_4") (pintype "passive"))
      (node (ref "R1") (pin "P$1") (pinfunction "1_P$1") (pintype "passive"))
      (node (ref "R10") (pin "P$1") (pinfunction "1_P$1") (pintype "passive"))
      (node (ref "R100") (pin "2") (pinfunction "2_2") (pintype "passive"))
      (node (ref "R11") (pin "P$1") (pinfunction "1_P$1") (pintype "passive"))
      (node (ref "R12") (pin "P$1") (pinfunction "1_P$1") (pintype "passive"))
      (node (ref "R13") (pin "P$2") (pinfunction "2_P$2") (pintype "passive"))
      (node (ref "R14") (pin "P$1") (pinfunction "1_P$1") (pintype "passive"))
      (node (ref "R15") (pin "P$1") (pinfunction "1_P$1") (pintype "passive"))
      (node (ref "R16") (pin "P$1") (pinfunction "1_P$1") (pintype "passive"))
      (node (ref "R17") (pin "P$1") (pinfunction "1_P$1") (pintype "passive"))
      (node (ref "R2") (pin "P$1") (pinfunction "1_P$1") (pintype "passive"))
      (node (ref "R23") (pin "P$2") (pinfunction "2_P$2") (pintype "passive"))
      (node (ref "R24") (pin "P$2") (pinfunction "2_P$2") (pintype "passive"))
      (node (ref "R25") (pin "P$2") (pinfunction "2_P$2") (pintype "passive"))
      (node (ref "R26") (pin "2") (pinfunction "2_2") (pintype "passive"))
      (node (ref "R27") (pin "P$2") (pinfunction "2_P$2") (pintype "passive"))
      (node (ref "R28") (pin "P$2") (pinfunction "2_P$2") (pintype "passive"))
      (node (ref "R29") (pin "P$2") (pinfunction "2_P$2") (pintype "passive"))
      (node (ref "R3") (pin "P$1") (pinfunction "1_P$1") (pintype "passive"))
      (node (ref "R30") (pin "P$2") (pinfunction "2_P$2") (pintype "passive"))
      (node (ref "R31") (pin "P$2") (pinfunction "2_P$2") (pintype "passive"))
      (node (ref "R32") (pin "P$2") (pinfunction "2_P$2") (pintype "passive"))
      (node (ref "R33") (pin "P$2") (pinfunction "2_P$2") (pintype "passive"))
      (node (ref "R35") (pin "P$2") (pinfunction "2_P$2") (pintype "passive"))
      (node (ref "R36") (pin "P$2") (pinfunction "2_P$2") (pintype "passive"))
      (node (ref "R37") (pin "P$2") (pinfunction "2_P$2") (pintype "passive"))
      (node (ref "R38") (pin "P$2") (pinfunction "2_P$2") (pintype "passive"))
      (node (ref "R39") (pin "P$2") (pinfunction "2_P$2") (pintype "passive"))
      (node (ref "R4") (pin "P$1") (pinfunction "1_P$1") (pintype "passive"))
      (node (ref "R40") (pin "P$2") (pinfunction "2_P$2") (pintype "passive"))
      (node (ref "R41") (pin "P$2") (pinfunction "2_P$2") (pintype "passive"))
      (node (ref "R43") (pin "P$2") (pinfunction "2_P$2") (pintype "passive"))
      (node (ref "R44") (pin "P$2") (pinfunction "2_P$2") (pintype "passive"))
      (node (ref "R45") (pin "P$2") (pinfunction "2_P$2") (pintype "passive"))
      (node (ref "R47") (pin "P$2") (pinfunction "2_P$2") (pintype "passive"))
      (node (ref "R48") (pin "P$2") (pinfunction "2_P$2") (pintype "passive"))
      (node (ref "R49") (pin "P$2") (pinfunction "2_P$2") (pintype "passive"))
      (node (ref "R5") (pin "P$1") (pinfunction "1_P$1") (pintype "passive"))
      (node (ref "R50") (pin "P$2") (pinfunction "2_P$2") (pintype "passive"))
      (node (ref "R51") (pin "P$2") (pinfunction "2_P$2") (pintype "passive"))
      (node (ref "R52") (pin "P$2") (pinfunction "2_P$2") (pintype "passive"))
      (node (ref "R53") (pin "P$2") (pinfunction "2_P$2") (pintype "passive"))
      (node (ref "R54") (pin "P$2") (pinfunction "2_P$2") (pintype "passive"))
      (node (ref "R55") (pin "P$2") (pinfunction "2_P$2") (pintype "passive"))
      (node (ref "R56") (pin "P$2") (pinfunction "2_P$2") (pintype "passive"))
      (node (ref "R57") (pin "P$2") (pinfunction "2_P$2") (pintype "passive"))
      (node (ref "R58") (pin "P$2") (pinfunction "2_P$2") (pintype "passive"))
      (node (ref "R59") (pin "P$2") (pinfunction "2_P$2") (pintype "passive"))
      (node (ref "R6") (pin "P$1") (pinfunction "1_P$1") (pintype "passive"))
      (node (ref "R60") (pin "P$2") (pinfunction "2_P$2") (pintype "passive"))
      (node (ref "R61") (pin "P$2") (pinfunction "2_P$2") (pintype "passive"))
      (node (ref "R62") (pin "P$2") (pinfunction "2_P$2") (pintype "passive"))
      (node (ref "R63") (pin "P$2") (pinfunction "2_P$2") (pintype "passive"))
      (node (ref "R64") (pin "P$2") (pinfunction "2_P$2") (pintype "passive"))
      (node (ref "R65") (pin "P$2") (pinfunction "2_P$2") (pintype "passive"))
      (node (ref "R66") (pin "P$2") (pinfunction "2_P$2") (pintype "passive"))
      (node (ref "R67") (pin "P$2") (pinfunction "2_P$2") (pintype "passive"))
      (node (ref "R68") (pin "P$2") (pinfunction "2_P$2") (pintype "passive"))
      (node (ref "R69") (pin "P$2") (pinfunction "2_P$2") (pintype "passive"))
      (node (ref "R7") (pin "P$1") (pinfunction "1_P$1") (pintype "passive"))
      (node (ref "R70") (pin "P$2") (pinfunction "2_P$2") (pintype "passive"))
      (node (ref "R71") (pin "P$2") (pinfunction "2_P$2") (pintype "passive"))
      (node (ref "R73") (pin "P$2") (pinfunction "2_P$2") (pintype "passive"))
      (node (ref "R74") (pin "2") (pinfunction "2_2") (pintype "passive"))
      (node (ref "R75") (pin "P$2") (pinfunction "2_P$2") (pintype "passive"))
      (node (ref "R76") (pin "P$2") (pinfunction "2_P$2") (pintype "passive"))
      (node (ref "R77") (pin "P$2") (pinfunction "2_P$2") (pintype "passive"))
      (node (ref "R79") (pin "P$2") (pinfunction "2_P$2") (pintype "passive"))
      (node (ref "R8") (pin "P$1") (pinfunction "1_P$1") (pintype "passive"))
      (node (ref "R80") (pin "P$2") (pinfunction "2_P$2") (pintype "passive"))
      (node (ref "R81") (pin "P$2") (pinfunction "2_P$2") (pintype "passive"))
      (node (ref "R82") (pin "2") (pinfunction "2_2") (pintype "passive"))
      (node (ref "R83") (pin "P$2") (pinfunction "2_P$2") (pintype "passive"))
      (node (ref "R84") (pin "P$2") (pinfunction "2_P$2") (pintype "passive"))
      (node (ref "R85") (pin "P$2") (pinfunction "2_P$2") (pintype "passive"))
      (node (ref "R87") (pin "P$2") (pinfunction "2_P$2") (pintype "passive"))
      (node (ref "R88") (pin "2") (pinfunction "2_2") (pintype "passive"))
      (node (ref "R89") (pin "P$2") (pinfunction "2_P$2") (pintype "passive"))
      (node (ref "R9") (pin "P$1") (pinfunction "1_P$1") (pintype "passive"))
      (node (ref "R91") (pin "P$2") (pinfunction "2_P$2") (pintype "passive"))
      (node (ref "R92") (pin "2") (pinfunction "2_2") (pintype "passive"))
      (node (ref "R93") (pin "P$2") (pinfunction "2_P$2") (pintype "passive"))
      (node (ref "R95") (pin "P$2") (pinfunction "2_P$2") (pintype "passive"))
      (node (ref "R96") (pin "2") (pinfunction "2_2") (pintype "passive"))
      (node (ref "R97") (pin "P$2") (pinfunction "2_P$2") (pintype "passive"))
      (node (ref "R98") (pin "2") (pinfunction "2_2") (pintype "passive"))
      (node (ref "R99") (pin "P$2") (pinfunction "2_P$2") (pintype "passive"))
      (node (ref "SW1") (pin "1") (pinfunction "1_1") (pintype "passive"))
      (node (ref "SW1") (pin "2") (pinfunction "2_2") (pintype "passive"))
      (node (ref "SW2") (pin "1") (pinfunction "1_1") (pintype "passive"))
      (node (ref "SW2") (pin "2") (pinfunction "2_2") (pintype "passive"))
      (node (ref "SW3") (pin "1") (pinfunction "1_1") (pintype "passive"))
      (node (ref "SW3") (pin "2") (pinfunction "2_2") (pintype "passive"))
      (node (ref "SW4") (pin "1") (pinfunction "1_1") (pintype "passive"))
      (node (ref "SW4") (pin "2") (pinfunction "2_2") (pintype "passive"))
    )
    (net (code "305") (name "VDD5") (class "Default")
      (node (ref "J1") (pin "5") (pinfunction "5_5") (pintype "passive"))
      (node (ref "J1") (pin "6") (pinfunction "6_6") (pintype "passive"))
    )
    (net (code "306") (name "VDD12") (class "Default")
      (node (ref "J1") (pin "7") (pinfunction "7_7") (pintype "passive"))
      (node (ref "J1") (pin "8") (pinfunction "8_8") (pintype "passive"))
    )
  )
)
